# DRIVERS.net
KiCad netlist of a schematic drawn in Altium Designer
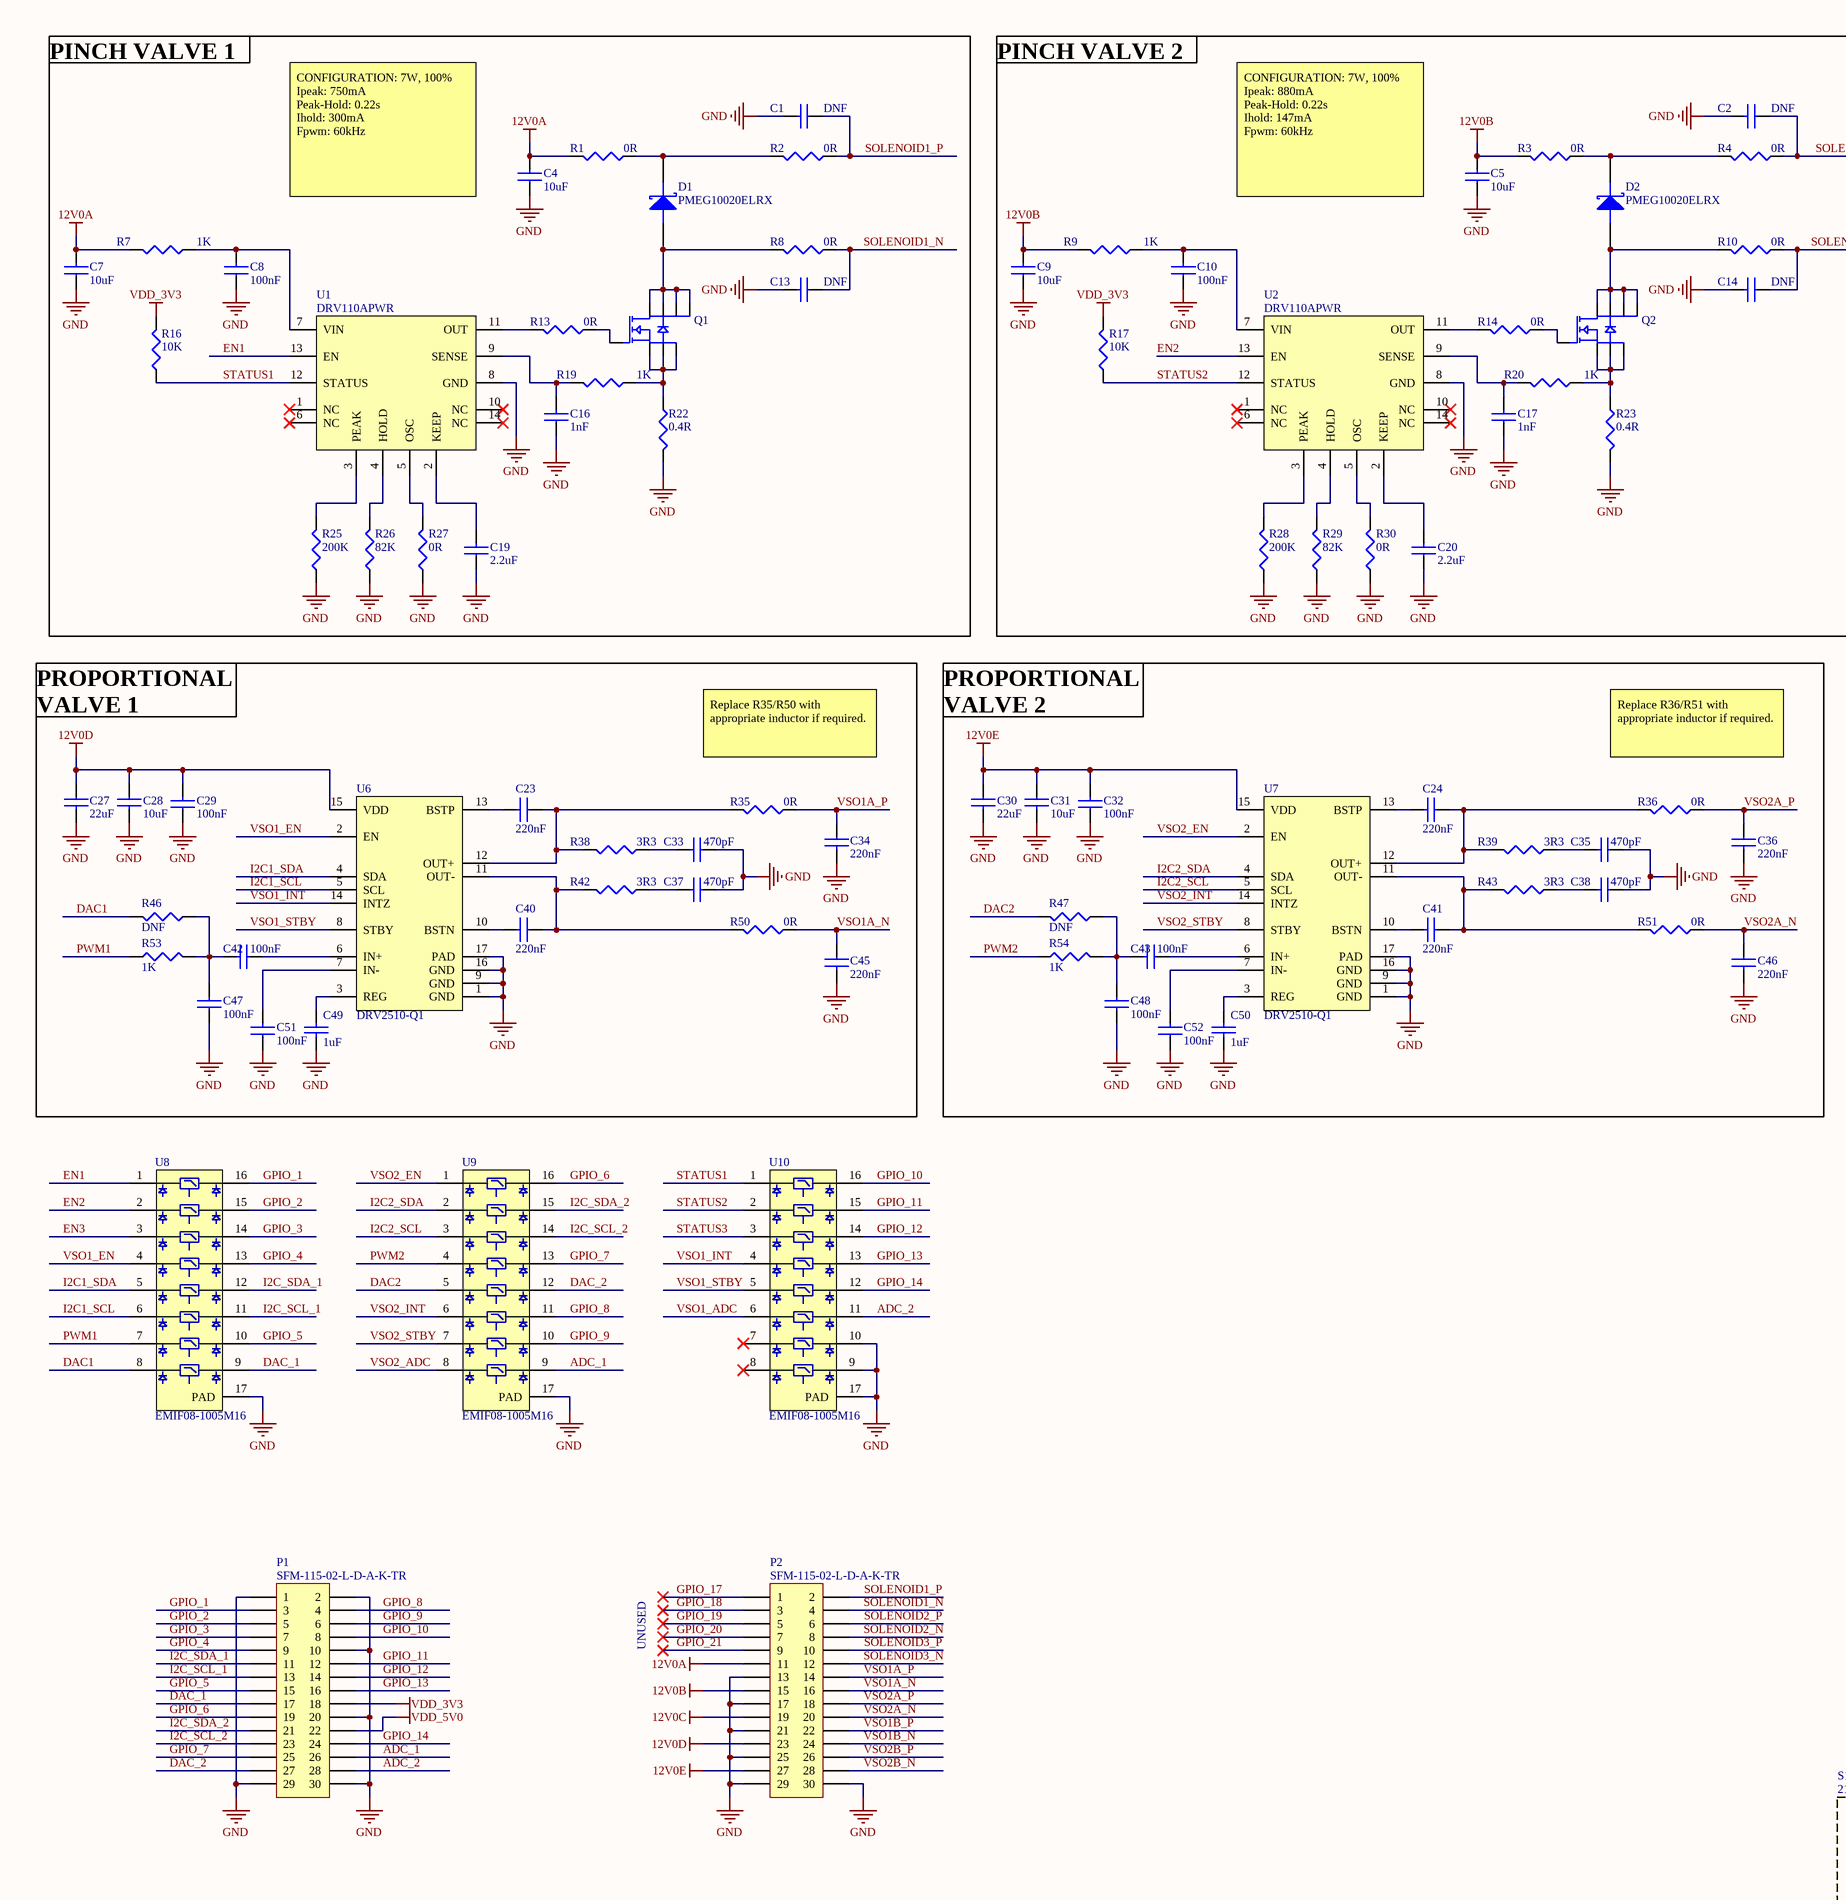
[diagram p0: DRIVERS.SchDoc, left]
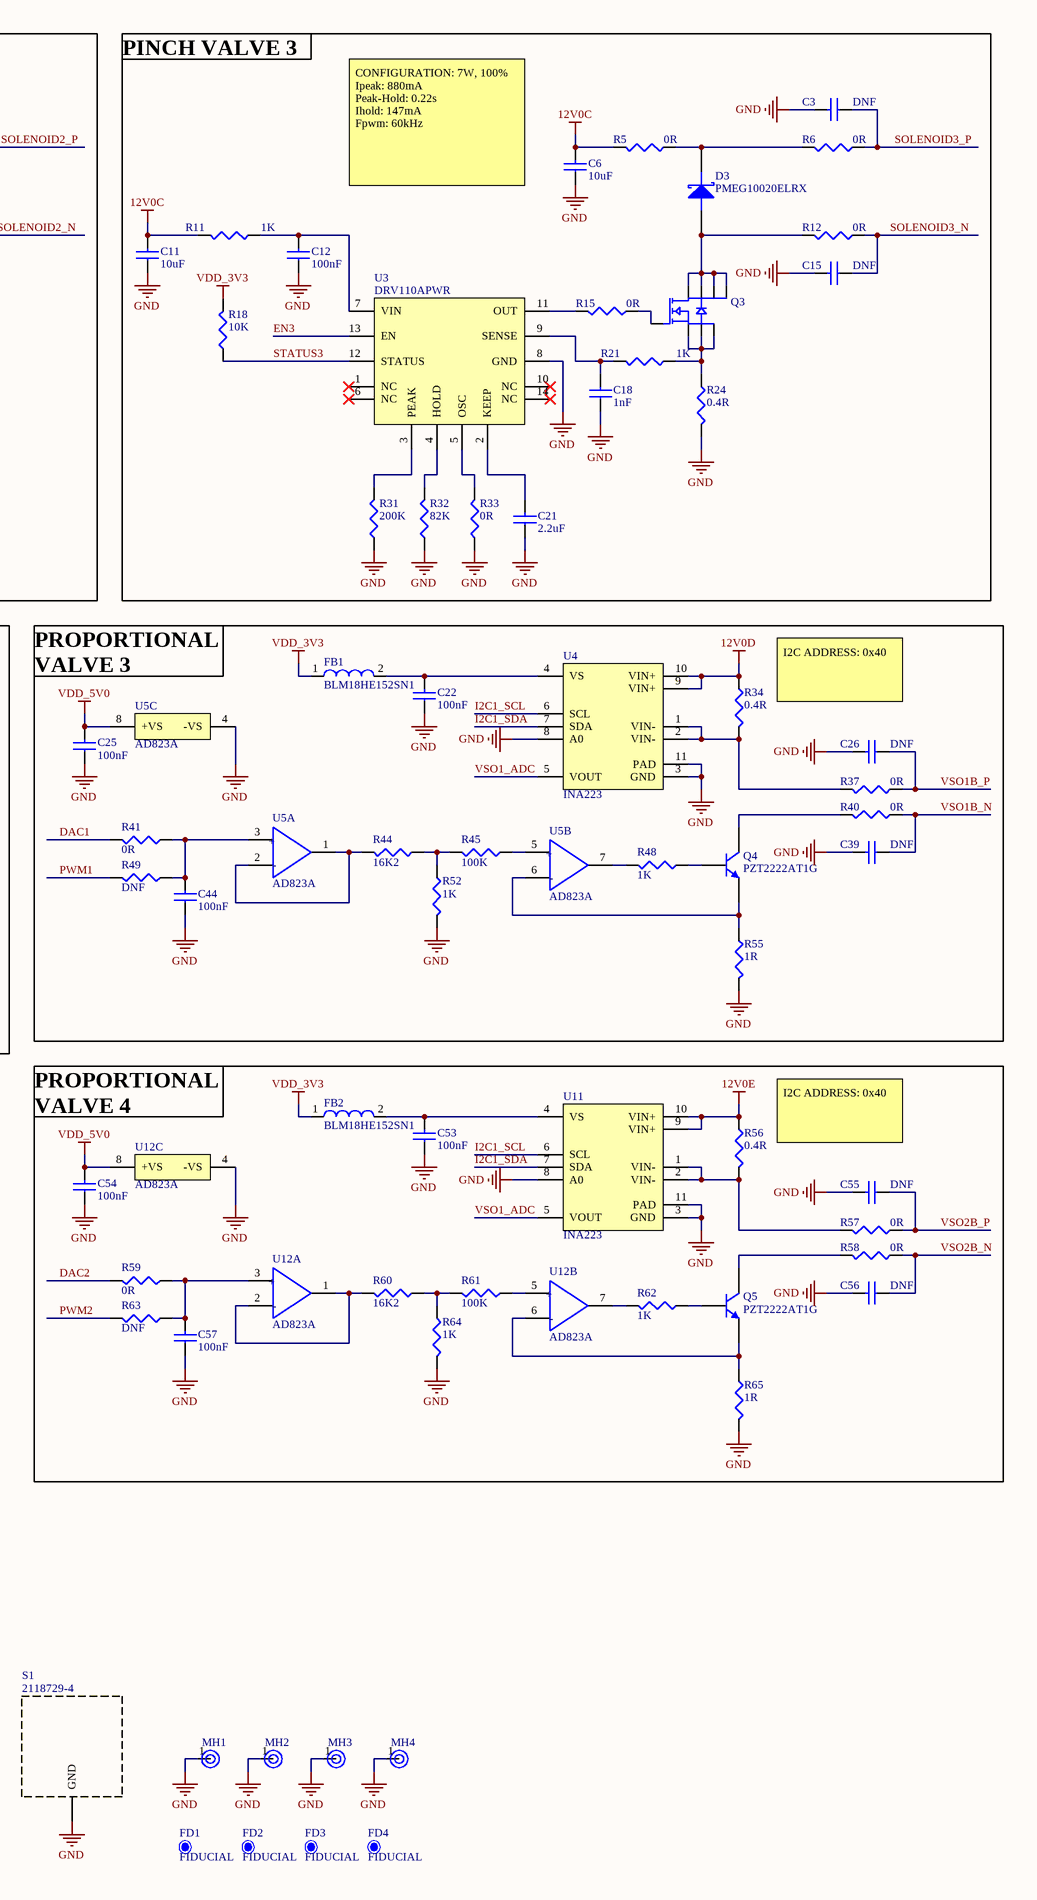
[diagram p1: DRIVERS.SchDoc, right]

(export (version "E")
  (design (tool "Eeschema 10.0.6"))
  (components
    (comp (ref "C1")
      (value "DNF")
      (footprint "CC0402")
      (description "CAP CER 0.001UF 50V 10% X7R 0402")
      (fields (field (name "MANUFACTURER") "Murata") (field (name "PARTNUMBER") "GCM155R71H102KA37D"))
      (libsource (lib "ERD TiAm") (part "CAP CER 0.1UF 10V 10% X5R 0402"))
    )
    (comp (ref "C2")
      (value "DNF")
      (footprint "CC0402")
      (description "CAP CER 0.001UF 50V 10% X7R 0402")
      (fields (field (name "MANUFACTURER") "Murata") (field (name "PARTNUMBER") "GCM155R71H102KA37D"))
      (libsource (lib "ERD TiAm") (part "CAP CER 0.1UF 10V 10% X5R 0402"))
    )
    (comp (ref "C3")
      (value "DNF")
      (footprint "CC0402")
      (description "CAP CER 0.001UF 50V 10% X7R 0402")
      (fields (field (name "MANUFACTURER") "Murata") (field (name "PARTNUMBER") "GCM155R71H102KA37D"))
      (libsource (lib "ERD TiAm") (part "CAP CER 0.1UF 10V 10% X5R 0402"))
    )
    (comp (ref "C4")
      (value "10uF")
      (footprint "CC0603")
      (description "CAP CER 10UF 25V 20% X5R 0603")
      (fields (field (name "MANUFACTURER") "Murata") (field (name "PARTNUMBER") "GRM188R61E106MA73D"))
      (libsource (lib "ERD TiAm") (part "CAP CER 0.1UF 10V 10% X5R 0402"))
    )
    (comp (ref "C5")
      (value "10uF")
      (footprint "CC0603")
      (description "CAP CER 10UF 25V 20% X5R 0603")
      (fields (field (name "MANUFACTURER") "Murata") (field (name "PARTNUMBER") "GRM188R61E106MA73D"))
      (libsource (lib "ERD TiAm") (part "CAP CER 0.1UF 10V 10% X5R 0402"))
    )
    (comp (ref "C6")
      (value "10uF")
      (footprint "CC0603")
      (description "CAP CER 10UF 25V 20% X5R 0603")
      (fields (field (name "MANUFACTURER") "Murata") (field (name "PARTNUMBER") "GRM188R61E106MA73D"))
      (libsource (lib "ERD TiAm") (part "CAP CER 0.1UF 10V 10% X5R 0402"))
    )
    (comp (ref "C7")
      (value "10uF")
      (footprint "CC0603")
      (description "CAP CER 10UF 25V 20% X5R 0603")
      (fields (field (name "MANUFACTURER") "Murata") (field (name "PARTNUMBER") "GRM188R61E106MA73D"))
      (libsource (lib "ERD TiAm") (part "CAP CER 0.1UF 10V 10% X5R 0402"))
    )
    (comp (ref "C8")
      (value "100nF")
      (footprint "CC0402")
      (description "CAP CER 0.1UF 50V 10% X7R 0402")
      (fields (field (name "MANUFACTURER") "Murata") (field (name "PARTNUMBER") "GCM155R71H104KE02D"))
      (libsource (lib "ERD TiAm") (part "CAP CER 0.1UF 10V 10% X5R 0402"))
    )
    (comp (ref "C9")
      (value "10uF")
      (footprint "CC0603")
      (description "CAP CER 10UF 25V 20% X5R 0603")
      (fields (field (name "MANUFACTURER") "Murata") (field (name "PARTNUMBER") "GRM188R61E106MA73D"))
      (libsource (lib "ERD TiAm") (part "CAP CER 0.1UF 10V 10% X5R 0402"))
    )
    (comp (ref "C10")
      (value "100nF")
      (footprint "CC0402")
      (description "CAP CER 0.1UF 50V 10% X7R 0402")
      (fields (field (name "MANUFACTURER") "Murata") (field (name "PARTNUMBER") "GCM155R71H104KE02D"))
      (libsource (lib "ERD TiAm") (part "CAP CER 0.1UF 10V 10% X5R 0402"))
    )
    (comp (ref "C11")
      (value "10uF")
      (footprint "CC0603")
      (description "CAP CER 10UF 25V 20% X5R 0603")
      (fields (field (name "MANUFACTURER") "Murata") (field (name "PARTNUMBER") "GRM188R61E106MA73D"))
      (libsource (lib "ERD TiAm") (part "CAP CER 0.1UF 10V 10% X5R 0402"))
    )
    (comp (ref "C12")
      (value "100nF")
      (footprint "CC0402")
      (description "CAP CER 0.1UF 50V 10% X7R 0402")
      (fields (field (name "MANUFACTURER") "Murata") (field (name "PARTNUMBER") "GCM155R71H104KE02D"))
      (libsource (lib "ERD TiAm") (part "CAP CER 0.1UF 10V 10% X5R 0402"))
    )
    (comp (ref "C13")
      (value "DNF")
      (footprint "CC0402")
      (description "CAP CER 0.001UF 50V 10% X7R 0402")
      (fields (field (name "MANUFACTURER") "Murata") (field (name "PARTNUMBER") "GCM155R71H102KA37D"))
      (libsource (lib "ERD TiAm") (part "CAP CER 0.1UF 10V 10% X5R 0402"))
    )
    (comp (ref "C14")
      (value "DNF")
      (footprint "CC0402")
      (description "CAP CER 0.001UF 50V 10% X7R 0402")
      (fields (field (name "MANUFACTURER") "Murata") (field (name "PARTNUMBER") "GCM155R71H102KA37D"))
      (libsource (lib "ERD TiAm") (part "CAP CER 0.1UF 10V 10% X5R 0402"))
    )
    (comp (ref "C15")
      (value "DNF")
      (footprint "CC0402")
      (description "CAP CER 0.001UF 50V 10% X7R 0402")
      (fields (field (name "MANUFACTURER") "Murata") (field (name "PARTNUMBER") "GCM155R71H102KA37D"))
      (libsource (lib "ERD TiAm") (part "CAP CER 0.1UF 10V 10% X5R 0402"))
    )
    (comp (ref "C16")
      (value "1nF")
      (footprint "CC0402")
      (description "CAP CER 0.001UF 50V 10% X7R 0402")
      (fields (field (name "MANUFACTURER") "Murata") (field (name "PARTNUMBER") "GCM155R71H102KA37D"))
      (libsource (lib "ERD TiAm") (part "CAP CER 0.1UF 10V 10% X5R 0402"))
    )
    (comp (ref "C17")
      (value "1nF")
      (footprint "CC0402")
      (description "CAP CER 0.001UF 50V 10% X7R 0402")
      (fields (field (name "MANUFACTURER") "Murata") (field (name "PARTNUMBER") "GCM155R71H102KA37D"))
      (libsource (lib "ERD TiAm") (part "CAP CER 0.1UF 10V 10% X5R 0402"))
    )
    (comp (ref "C18")
      (value "1nF")
      (footprint "CC0402")
      (description "CAP CER 0.001UF 50V 10% X7R 0402")
      (fields (field (name "MANUFACTURER") "Murata") (field (name "PARTNUMBER") "GCM155R71H102KA37D"))
      (libsource (lib "ERD TiAm") (part "CAP CER 0.1UF 10V 10% X5R 0402"))
    )
    (comp (ref "C19")
      (value "2.2uF")
      (footprint "CC0603")
      (description "CAP CER 2.2UF 25V 10% X5R 0603")
      (fields (field (name "MANUFACTURER") "Murata") (field (name "PARTNUMBER") "GRM188R61E225KA12D"))
      (libsource (lib "ERD TiAm") (part "CAP CER 0.1UF 10V 10% X5R 0402"))
    )
    (comp (ref "C20")
      (value "2.2uF")
      (footprint "CC0603")
      (description "CAP CER 2.2UF 25V 10% X5R 0603")
      (fields (field (name "MANUFACTURER") "Murata") (field (name "PARTNUMBER") "GRM188R61E225KA12D"))
      (libsource (lib "ERD TiAm") (part "CAP CER 0.1UF 10V 10% X5R 0402"))
    )
    (comp (ref "C21")
      (value "2.2uF")
      (footprint "CC0603")
      (description "CAP CER 2.2UF 25V 10% X5R 0603")
      (fields (field (name "MANUFACTURER") "Murata") (field (name "PARTNUMBER") "GRM188R61E225KA12D"))
      (libsource (lib "ERD TiAm") (part "CAP CER 0.1UF 10V 10% X5R 0402"))
    )
    (comp (ref "C22")
      (value "100nF")
      (footprint "CC0402")
      (description "CAP CER 0.1UF 50V 10% X7R 0402")
      (fields (field (name "MANUFACTURER") "Murata") (field (name "PARTNUMBER") "GCM155R71H104KE02D"))
      (libsource (lib "ERD TiAm") (part "CAP CER 0.1UF 10V 10% X5R 0402"))
    )
    (comp (ref "C23")
      (value "220nF")
      (footprint "CC0603")
      (description "CAP CER 0.22UF 25V 10% X7R 0603")
      (fields (field (name "MANUFACTURER") "Murata") (field (name "PARTNUMBER") "GRM188R71E224KA88D"))
      (libsource (lib "ERD TiAm") (part "CAP CER 0.1UF 10V 10% X5R 0402"))
    )
    (comp (ref "C24")
      (value "220nF")
      (footprint "CC0603")
      (description "CAP CER 0.22UF 25V 10% X7R 0603")
      (fields (field (name "MANUFACTURER") "Murata") (field (name "PARTNUMBER") "GRM188R71E224KA88D"))
      (libsource (lib "ERD TiAm") (part "CAP CER 0.1UF 10V 10% X5R 0402"))
    )
    (comp (ref "C25")
      (value "100nF")
      (footprint "CC0402")
      (description "CAP CER 0.1UF 50V 10% X7R 0402")
      (fields (field (name "MANUFACTURER") "Murata") (field (name "PARTNUMBER") "GCM155R71H104KE02D"))
      (libsource (lib "ERD TiAm") (part "CAP CER 0.1UF 10V 10% X5R 0402"))
    )
    (comp (ref "C26")
      (value "DNF")
      (footprint "CC0402")
      (description "CAP CER 0.001UF 50V 10% X7R 0402")
      (fields (field (name "MANUFACTURER") "Murata") (field (name "PARTNUMBER") "GCM155R71H102KA37D"))
      (libsource (lib "ERD TiAm") (part "CAP CER 0.1UF 10V 10% X5R 0402"))
    )
    (comp (ref "C27")
      (value "22uF")
      (footprint "CC0805")
      (description "CAP CER 22UF 25V 20% X5R 0805")
      (fields (field (name "MANUFACTURER") "Murata") (field (name "PARTNUMBER") "GRM21BR61E226ME44K"))
      (libsource (lib "ERD TiAm") (part "CAP CER 0.1UF 10V 10% X5R 0402"))
    )
    (comp (ref "C28")
      (value "10uF")
      (footprint "CC0603")
      (description "CAP CER 10UF 25V 20% X5R 0603")
      (fields (field (name "MANUFACTURER") "Murata") (field (name "PARTNUMBER") "GRM188R61E106MA73D"))
      (libsource (lib "ERD TiAm") (part "CAP CER 0.1UF 10V 10% X5R 0402"))
    )
    (comp (ref "C29")
      (value "100nF")
      (footprint "CC0402")
      (description "CAP CER 0.1UF 50V 10% X7R 0402")
      (fields (field (name "MANUFACTURER") "Murata") (field (name "PARTNUMBER") "GCM155R71H104KE02D"))
      (libsource (lib "ERD TiAm") (part "CAP CER 0.1UF 10V 10% X5R 0402"))
    )
    (comp (ref "C30")
      (value "22uF")
      (footprint "CC0805")
      (description "CAP CER 22UF 25V 20% X5R 0805")
      (fields (field (name "MANUFACTURER") "Murata") (field (name "PARTNUMBER") "GRM21BR61E226ME44K"))
      (libsource (lib "ERD TiAm") (part "CAP CER 0.1UF 10V 10% X5R 0402"))
    )
    (comp (ref "C31")
      (value "10uF")
      (footprint "CC0603")
      (description "CAP CER 10UF 25V 20% X5R 0603")
      (fields (field (name "MANUFACTURER") "Murata") (field (name "PARTNUMBER") "GRM188R61E106MA73D"))
      (libsource (lib "ERD TiAm") (part "CAP CER 0.1UF 10V 10% X5R 0402"))
    )
    (comp (ref "C32")
      (value "100nF")
      (footprint "CC0402")
      (description "CAP CER 0.1UF 50V 10% X7R 0402")
      (fields (field (name "MANUFACTURER") "Murata") (field (name "PARTNUMBER") "GCM155R71H104KE02D"))
      (libsource (lib "ERD TiAm") (part "CAP CER 0.1UF 10V 10% X5R 0402"))
    )
    (comp (ref "C33")
      (value "470pF")
      (footprint "CC0603")
      (description "CAP CER 470PF 50V 5% C0G/NP0 0402")
      (fields (field (name "MANUFACTURER") "Murata") (field (name "PARTNUMBER") "GRM1555C1H471JA01D"))
      (libsource (lib "ERD TiAm") (part "CAP CER 0.1UF 10V 10% X5R 0402"))
    )
    (comp (ref "C34")
      (value "220nF")
      (footprint "CC0603")
      (description "CAP CER 0.22UF 25V 10% X7R 0603")
      (fields (field (name "MANUFACTURER") "Murata") (field (name "PARTNUMBER") "GRM188R71E224KA88D"))
      (libsource (lib "ERD TiAm") (part "CAP CER 0.1UF 10V 10% X5R 0402"))
    )
    (comp (ref "C35")
      (value "470pF")
      (footprint "CC0603")
      (description "CAP CER 470PF 50V 5% C0G/NP0 0402")
      (fields (field (name "MANUFACTURER") "Murata") (field (name "PARTNUMBER") "GRM1555C1H471JA01D"))
      (libsource (lib "ERD TiAm") (part "CAP CER 0.1UF 10V 10% X5R 0402"))
    )
    (comp (ref "C36")
      (value "220nF")
      (footprint "CC0603")
      (description "CAP CER 0.22UF 25V 10% X7R 0603")
      (fields (field (name "MANUFACTURER") "Murata") (field (name "PARTNUMBER") "GRM188R71E224KA88D"))
      (libsource (lib "ERD TiAm") (part "CAP CER 0.1UF 10V 10% X5R 0402"))
    )
    (comp (ref "C37")
      (value "470pF")
      (footprint "CC0603")
      (description "CAP CER 470PF 50V 5% C0G/NP0 0402")
      (fields (field (name "MANUFACTURER") "Murata") (field (name "PARTNUMBER") "GRM1555C1H471JA01D"))
      (libsource (lib "ERD TiAm") (part "CAP CER 0.1UF 10V 10% X5R 0402"))
    )
    (comp (ref "C38")
      (value "470pF")
      (footprint "CC0603")
      (description "CAP CER 470PF 50V 5% C0G/NP0 0402")
      (fields (field (name "MANUFACTURER") "Murata") (field (name "PARTNUMBER") "GRM1555C1H471JA01D"))
      (libsource (lib "ERD TiAm") (part "CAP CER 0.1UF 10V 10% X5R 0402"))
    )
    (comp (ref "C39")
      (value "DNF")
      (footprint "CC0402")
      (description "CAP CER 0.001UF 50V 10% X7R 0402")
      (fields (field (name "MANUFACTURER") "Murata") (field (name "PARTNUMBER") "GCM155R71H102KA37D"))
      (libsource (lib "ERD TiAm") (part "CAP CER 0.1UF 10V 10% X5R 0402"))
    )
    (comp (ref "C40")
      (value "220nF")
      (footprint "CC0603")
      (description "CAP CER 0.22UF 25V 10% X7R 0603")
      (fields (field (name "MANUFACTURER") "Murata") (field (name "PARTNUMBER") "GRM188R71E224KA88D"))
      (libsource (lib "ERD TiAm") (part "CAP CER 0.1UF 10V 10% X5R 0402"))
    )
    (comp (ref "C41")
      (value "220nF")
      (footprint "CC0603")
      (description "CAP CER 0.22UF 25V 10% X7R 0603")
      (fields (field (name "MANUFACTURER") "Murata") (field (name "PARTNUMBER") "GRM188R71E224KA88D"))
      (libsource (lib "ERD TiAm") (part "CAP CER 0.1UF 10V 10% X5R 0402"))
    )
    (comp (ref "C42")
      (value "100nF")
      (footprint "CC0402")
      (description "CAP CER 0.1UF 50V 10% X7R 0402")
      (fields (field (name "MANUFACTURER") "Murata") (field (name "PARTNUMBER") "GCM155R71H104KE02D"))
      (libsource (lib "ERD TiAm") (part "CAP CER 0.1UF 10V 10% X5R 0402"))
    )
    (comp (ref "C43")
      (value "100nF")
      (footprint "CC0402")
      (description "CAP CER 0.1UF 50V 10% X7R 0402")
      (fields (field (name "MANUFACTURER") "Murata") (field (name "PARTNUMBER") "GCM155R71H104KE02D"))
      (libsource (lib "ERD TiAm") (part "CAP CER 0.1UF 10V 10% X5R 0402"))
    )
    (comp (ref "C44")
      (value "100nF")
      (footprint "CC0402")
      (description "CAP CER 0.1UF 50V 10% X7R 0402")
      (fields (field (name "MANUFACTURER") "Murata") (field (name "PARTNUMBER") "GCM155R71H104KE02D"))
      (libsource (lib "ERD TiAm") (part "CAP CER 0.1UF 10V 10% X5R 0402"))
    )
    (comp (ref "C45")
      (value "220nF")
      (footprint "CC0603")
      (description "CAP CER 0.22UF 25V 10% X7R 0603")
      (fields (field (name "MANUFACTURER") "Murata") (field (name "PARTNUMBER") "GRM188R71E224KA88D"))
      (libsource (lib "ERD TiAm") (part "CAP CER 0.1UF 10V 10% X5R 0402"))
    )
    (comp (ref "C46")
      (value "220nF")
      (footprint "CC0603")
      (description "CAP CER 0.22UF 25V 10% X7R 0603")
      (fields (field (name "MANUFACTURER") "Murata") (field (name "PARTNUMBER") "GRM188R71E224KA88D"))
      (libsource (lib "ERD TiAm") (part "CAP CER 0.1UF 10V 10% X5R 0402"))
    )
    (comp (ref "C47")
      (value "100nF")
      (footprint "CC0402")
      (description "CAP CER 0.1UF 50V 10% X7R 0402")
      (fields (field (name "MANUFACTURER") "Murata") (field (name "PARTNUMBER") "GCM155R71H104KE02D"))
      (libsource (lib "ERD TiAm") (part "CAP CER 0.1UF 10V 10% X5R 0402"))
    )
    (comp (ref "C48")
      (value "100nF")
      (footprint "CC0402")
      (description "CAP CER 0.1UF 50V 10% X7R 0402")
      (fields (field (name "MANUFACTURER") "Murata") (field (name "PARTNUMBER") "GCM155R71H104KE02D"))
      (libsource (lib "ERD TiAm") (part "CAP CER 0.1UF 10V 10% X5R 0402"))
    )
    (comp (ref "C49")
      (value "1uF")
      (footprint "CC0402")
      (description "CAP CER 1.0UF 10V 10% X5R 0402")
      (fields (field (name "PARTNUMBER") "GRM153R61A105ME95D"))
      (libsource (lib "*") (part "CAPCERAMIC"))
    )
    (comp (ref "C50")
      (value "1uF")
      (footprint "CC0402")
      (description "CAP CER 1.0UF 10V 10% X5R 0402")
      (fields (field (name "PARTNUMBER") "GRM153R61A105ME95D"))
      (libsource (lib "*") (part "CAPCERAMIC"))
    )
    (comp (ref "C51")
      (value "100nF")
      (footprint "CC0402")
      (description "CAP CER 0.1UF 50V 10% X7R 0402")
      (fields (field (name "MANUFACTURER") "Murata") (field (name "PARTNUMBER") "GCM155R71H104KE02D"))
      (libsource (lib "ERD TiAm") (part "CAP CER 0.1UF 10V 10% X5R 0402"))
    )
    (comp (ref "C52")
      (value "100nF")
      (footprint "CC0402")
      (description "CAP CER 0.1UF 50V 10% X7R 0402")
      (fields (field (name "MANUFACTURER") "Murata") (field (name "PARTNUMBER") "GCM155R71H104KE02D"))
      (libsource (lib "ERD TiAm") (part "CAP CER 0.1UF 10V 10% X5R 0402"))
    )
    (comp (ref "C53")
      (value "100nF")
      (footprint "CC0402")
      (description "CAP CER 0.1UF 50V 10% X7R 0402")
      (fields (field (name "MANUFACTURER") "Murata") (field (name "PARTNUMBER") "GCM155R71H104KE02D"))
      (libsource (lib "ERD TiAm") (part "CAP CER 0.1UF 10V 10% X5R 0402"))
    )
    (comp (ref "C54")
      (value "100nF")
      (footprint "CC0402")
      (description "CAP CER 0.1UF 50V 10% X7R 0402")
      (fields (field (name "MANUFACTURER") "Murata") (field (name "PARTNUMBER") "GCM155R71H104KE02D"))
      (libsource (lib "ERD TiAm") (part "CAP CER 0.1UF 10V 10% X5R 0402"))
    )
    (comp (ref "C55")
      (value "DNF")
      (footprint "CC0402")
      (description "CAP CER 0.001UF 50V 10% X7R 0402")
      (fields (field (name "MANUFACTURER") "Murata") (field (name "PARTNUMBER") "GCM155R71H102KA37D"))
      (libsource (lib "ERD TiAm") (part "CAP CER 0.1UF 10V 10% X5R 0402"))
    )
    (comp (ref "C56")
      (value "DNF")
      (footprint "CC0402")
      (description "CAP CER 0.001UF 50V 10% X7R 0402")
      (fields (field (name "MANUFACTURER") "Murata") (field (name "PARTNUMBER") "GCM155R71H102KA37D"))
      (libsource (lib "ERD TiAm") (part "CAP CER 0.1UF 10V 10% X5R 0402"))
    )
    (comp (ref "C57")
      (value "100nF")
      (footprint "CC0402")
      (description "CAP CER 0.1UF 50V 10% X7R 0402")
      (fields (field (name "MANUFACTURER") "Murata") (field (name "PARTNUMBER") "GCM155R71H104KE02D"))
      (libsource (lib "ERD TiAm") (part "CAP CER 0.1UF 10V 10% X5R 0402"))
    )
    (comp (ref "D1")
      (value "PMEG10020ELRX")
      (footprint "SOD123W")
      (description "DIODE, SCHOTTKY, 100V, 2A, 3.7ns, SOD123W")
      (libsource (lib "GadgetJD") (part "DIODE SCHOTTKY"))
    )
    (comp (ref "D2")
      (value "PMEG10020ELRX")
      (footprint "SOD123W")
      (description "DIODE, SCHOTTKY, 100V, 2A, 3.7ns, SOD123W")
      (libsource (lib "GadgetJD") (part "DIODE SCHOTTKY"))
    )
    (comp (ref "D3")
      (value "PMEG10020ELRX")
      (footprint "SOD123W")
      (description "DIODE, SCHOTTKY, 100V, 2A, 3.7ns, SOD123W")
      (libsource (lib "GadgetJD") (part "DIODE SCHOTTKY"))
    )
    (comp (ref "FB1")
      (value "BLM18HE152SN1")
      (footprint "LC0603")
      (description "FERRITE, 500mA, 500mOHM, 0603")
      (libsource (lib "BEAGLEBONEBLACK_REV A5B") (part "FER_180_200_0"))
    )
    (comp (ref "FB2")
      (value "BLM18HE152SN1")
      (footprint "LC0603")
      (description "FERRITE, 500mA, 500mOHM, 0603")
      (libsource (lib "BEAGLEBONEBLACK_REV A5B") (part "FER_180_200_0"))
    )
    (comp (ref "FD1")
      (value "FIDUCIAL")
      (footprint "FIDUCIAL")
      (description "Fiducial 2mm")
      (fields (field (name "PARTNUMBER") "NA"))
      (libsource (lib "*") (part "FIDUCIAL"))
    )
    (comp (ref "FD2")
      (value "FIDUCIAL")
      (footprint "FIDUCIAL")
      (description "Fiducial 2mm")
      (fields (field (name "PARTNUMBER") "NA"))
      (libsource (lib "*") (part "FIDUCIAL"))
    )
    (comp (ref "FD3")
      (value "FIDUCIAL")
      (footprint "FIDUCIAL")
      (description "Fiducial 2mm")
      (fields (field (name "PARTNUMBER") "NA"))
      (libsource (lib "*") (part "FIDUCIAL"))
    )
    (comp (ref "FD4")
      (value "FIDUCIAL")
      (footprint "FIDUCIAL")
      (description "Fiducial 2mm")
      (fields (field (name "PARTNUMBER") "NA"))
      (libsource (lib "*") (part "FIDUCIAL"))
    )
    (comp (ref "MH1")
      (value "MH")
      (footprint "MH - M3")
      (description "Mounting Hole")
      (fields (field (name "PARTNUMBER") "NA"))
      (libsource (lib "BCI_rev_0") (part "MountingHole"))
    )
    (comp (ref "MH2")
      (value "MH")
      (footprint "MH - M3")
      (description "Mounting Hole")
      (fields (field (name "PARTNUMBER") "NA"))
      (libsource (lib "BCI_rev_0") (part "MountingHole"))
    )
    (comp (ref "MH3")
      (value "MH")
      (footprint "MH - M3")
      (description "Mounting Hole")
      (fields (field (name "PARTNUMBER") "NA"))
      (libsource (lib "BCI_rev_0") (part "MountingHole"))
    )
    (comp (ref "MH4")
      (value "MH")
      (footprint "MH - M3")
      (description "Mounting Hole")
      (fields (field (name "PARTNUMBER") "NA"))
      (libsource (lib "BCI_rev_0") (part "MountingHole"))
    )
    (comp (ref "P1")
      (value "SFM-115-02-L-D-A-K-TR")
      (footprint "ERD TiAm:SFM-115-02-L-D-A-K-TR")
      (description "Receptacle, 30 POS, 1.27mm PITCH, SMD")
      (libsource (lib "Miscellaneous Connectors") (part "Header 15X2"))
    )
    (comp (ref "P2")
      (value "SFM-115-02-L-D-A-K-TR")
      (footprint "ERD TiAm:SFM-115-02-L-D-A-K-TR")
      (description "Receptacle, 30 POS, 1.27mm PITCH, SMD")
      (libsource (lib "Miscellaneous Connectors") (part "Header 15X2"))
    )
    (comp (ref "Q1")
      (value "BSC054N04NSGATMA1")
      (footprint "PG-TDSON-8 - alternate")
      (description "N-channel FET, 40V, 17A, 5.4mOhm, TDSON-8")
      (libsource (lib "SCH") (part "BSC190N15NS3"))
    )
    (comp (ref "Q2")
      (value "BSC054N04NSGATMA1")
      (footprint "PG-TDSON-8 - alternate")
      (description "N-channel FET, 40V, 17A, 5.4mOhm, TDSON-8")
      (libsource (lib "SCH") (part "BSC190N15NS3"))
    )
    (comp (ref "Q3")
      (value "BSC054N04NSGATMA1")
      (footprint "PG-TDSON-8 - alternate")
      (description "N-channel FET, 40V, 17A, 5.4mOhm, TDSON-8")
      (libsource (lib "SCH") (part "BSC190N15NS3"))
    )
    (comp (ref "Q4")
      (value "PZT2222AT1G")
      (footprint "ERD TiAm:SOT223")
      (description "NPN BJT, 600 mA, 40V, SOT223")
      (fields (field (name "MANUFACTURER") "ON Semiconductor"))
      (libsource (lib "Miscellaneous Devices") (part "NPN"))
    )
    (comp (ref "Q5")
      (value "PZT2222AT1G")
      (footprint "ERD TiAm:SOT223")
      (description "NPN BJT, 600 mA, 40V, SOT223")
      (fields (field (name "MANUFACTURER") "ON Semiconductor"))
      (libsource (lib "Miscellaneous Devices") (part "NPN"))
    )
    (comp (ref "R1")
      (value "0R")
      (footprint "RC0603")
      (description "RES, 0 OHM, 1/10W, 50mOhm (5%), 0603")
      (fields (field (name "MANUFACTURER") "Yageo") (field (name "PARTNUMBER") "RC0603JR-070RP"))
      (libsource (lib "ERD TiAm") (part "RES_10K_1/16W_1%_0402"))
    )
    (comp (ref "R2")
      (value "0R")
      (footprint "RC0603")
      (description "RES, 0 OHM, 1/10W, 50mOhm (5%), 0603")
      (fields (field (name "MANUFACTURER") "Yageo") (field (name "PARTNUMBER") "RC0603JR-070RP"))
      (libsource (lib "ERD TiAm") (part "RES_10K_1/16W_1%_0402"))
    )
    (comp (ref "R3")
      (value "0R")
      (footprint "RC0603")
      (description "RES, 0 OHM, 1/10W, 50mOhm (5%), 0603")
      (fields (field (name "MANUFACTURER") "Yageo") (field (name "PARTNUMBER") "RC0603JR-070RP"))
      (libsource (lib "ERD TiAm") (part "RES_10K_1/16W_1%_0402"))
    )
    (comp (ref "R4")
      (value "0R")
      (footprint "RC0603")
      (description "RES, 0 OHM, 1/10W, 50mOhm (5%), 0603")
      (fields (field (name "MANUFACTURER") "Yageo") (field (name "PARTNUMBER") "RC0603JR-070RP"))
      (libsource (lib "ERD TiAm") (part "RES_10K_1/16W_1%_0402"))
    )
    (comp (ref "R5")
      (value "0R")
      (footprint "RC0603")
      (description "RES, 0 OHM, 1/10W, 50mOhm (5%), 0603")
      (fields (field (name "MANUFACTURER") "Yageo") (field (name "PARTNUMBER") "RC0603JR-070RP"))
      (libsource (lib "ERD TiAm") (part "RES_10K_1/16W_1%_0402"))
    )
    (comp (ref "R6")
      (value "0R")
      (footprint "RC0603")
      (description "RES, 0 OHM, 1/10W, 50mOhm (5%), 0603")
      (fields (field (name "MANUFACTURER") "Yageo") (field (name "PARTNUMBER") "RC0603JR-070RP"))
      (libsource (lib "ERD TiAm") (part "RES_10K_1/16W_1%_0402"))
    )
    (comp (ref "R7")
      (value "1K")
      (footprint "RC0402")
      (description "RES, 1K OHM, 1/16W, 1%, 0402")
      (fields (field (name "MANUFACTURER") "Yageo") (field (name "PARTNUMBER") "RC0402FR-071KL"))
      (libsource (lib "ERD TiAm") (part "RES_10K_1/16W_1%_0402"))
    )
    (comp (ref "R8")
      (value "0R")
      (footprint "RC0603")
      (description "RES, 0 OHM, 1/10W, 50mOhm (5%), 0603")
      (fields (field (name "MANUFACTURER") "Yageo") (field (name "PARTNUMBER") "RC0603JR-070RP"))
      (libsource (lib "ERD TiAm") (part "RES_10K_1/16W_1%_0402"))
    )
    (comp (ref "R9")
      (value "1K")
      (footprint "RC0402")
      (description "RES, 1K OHM, 1/16W, 1%, 0402")
      (fields (field (name "MANUFACTURER") "Yageo") (field (name "PARTNUMBER") "RC0402FR-071KL"))
      (libsource (lib "ERD TiAm") (part "RES_10K_1/16W_1%_0402"))
    )
    (comp (ref "R10")
      (value "0R")
      (footprint "RC0603")
      (description "RES, 0 OHM, 1/10W, 50mOhm (5%), 0603")
      (fields (field (name "MANUFACTURER") "Yageo") (field (name "PARTNUMBER") "RC0603JR-070RP"))
      (libsource (lib "ERD TiAm") (part "RES_10K_1/16W_1%_0402"))
    )
    (comp (ref "R11")
      (value "1K")
      (footprint "RC0402")
      (description "RES, 1K OHM, 1/16W, 1%, 0402")
      (fields (field (name "MANUFACTURER") "Yageo") (field (name "PARTNUMBER") "RC0402FR-071KL"))
      (libsource (lib "ERD TiAm") (part "RES_10K_1/16W_1%_0402"))
    )
    (comp (ref "R12")
      (value "0R")
      (footprint "RC0603")
      (description "RES, 0 OHM, 1/10W, 50mOhm (5%), 0603")
      (fields (field (name "MANUFACTURER") "Yageo") (field (name "PARTNUMBER") "RC0603JR-070RP"))
      (libsource (lib "ERD TiAm") (part "RES_10K_1/16W_1%_0402"))
    )
    (comp (ref "R13")
      (value "0R")
      (footprint "RC0402")
      (description "RES, 0 OHM, 1/16W, 1%, 0402")
      (fields (field (name "MANUFACTURER") "Yageo") (field (name "PARTNUMBER") "RC0402FR-070RL"))
      (libsource (lib "ERD TiAm") (part "RES_10K_1/16W_1%_0402"))
    )
    (comp (ref "R14")
      (value "0R")
      (footprint "RC0402")
      (description "RES, 0 OHM, 1/16W, 1%, 0402")
      (fields (field (name "MANUFACTURER") "Yageo") (field (name "PARTNUMBER") "RC0402FR-070RL"))
      (libsource (lib "ERD TiAm") (part "RES_10K_1/16W_1%_0402"))
    )
    (comp (ref "R15")
      (value "0R")
      (footprint "RC0402")
      (description "RES, 0 OHM, 1/16W, 1%, 0402")
      (fields (field (name "MANUFACTURER") "Yageo") (field (name "PARTNUMBER") "RC0402FR-070RL"))
      (libsource (lib "ERD TiAm") (part "RES_10K_1/16W_1%_0402"))
    )
    (comp (ref "R16")
      (value "10K")
      (footprint "RC0402")
      (description "RES, 10K OHM, 1/16W, 1%, 0402")
      (fields (field (name "MANUFACTURER") "Yageo") (field (name "PARTNUMBER") "RC0402FR-0710KL"))
      (libsource (lib "ERD TiAm") (part "RES_10K_1/16W_1%_0402"))
    )
    (comp (ref "R17")
      (value "10K")
      (footprint "RC0402")
      (description "RES, 10K OHM, 1/16W, 1%, 0402")
      (fields (field (name "MANUFACTURER") "Yageo") (field (name "PARTNUMBER") "RC0402FR-0710KL"))
      (libsource (lib "ERD TiAm") (part "RES_10K_1/16W_1%_0402"))
    )
    (comp (ref "R18")
      (value "10K")
      (footprint "RC0402")
      (description "RES, 10K OHM, 1/16W, 1%, 0402")
      (fields (field (name "MANUFACTURER") "Yageo") (field (name "PARTNUMBER") "RC0402FR-0710KL"))
      (libsource (lib "ERD TiAm") (part "RES_10K_1/16W_1%_0402"))
    )
    (comp (ref "R19")
      (value "1K")
      (footprint "RC0402")
      (description "RES, 1K OHM, 1/16W, 1%, 0402")
      (fields (field (name "MANUFACTURER") "Yageo") (field (name "PARTNUMBER") "RC0402FR-071KL"))
      (libsource (lib "ERD TiAm") (part "RES_10K_1/16W_1%_0402"))
    )
    (comp (ref "R20")
      (value "1K")
      (footprint "RC0402")
      (description "RES, 1K OHM, 1/16W, 1%, 0402")
      (fields (field (name "MANUFACTURER") "Yageo") (field (name "PARTNUMBER") "RC0402FR-071KL"))
      (libsource (lib "ERD TiAm") (part "RES_10K_1/16W_1%_0402"))
    )
    (comp (ref "R21")
      (value "1K")
      (footprint "RC0402")
      (description "RES, 1K OHM, 1/16W, 1%, 0402")
      (fields (field (name "MANUFACTURER") "Yageo") (field (name "PARTNUMBER") "RC0402FR-071KL"))
      (libsource (lib "ERD TiAm") (part "RES_10K_1/16W_1%_0402"))
    )
    (comp (ref "R22")
      (value "0.4R")
      (footprint "RC1210")
      (description "RES, 0.4 OHM, 1/2W, 1%, 2010")
      (fields (field (name "MANUFACTURER") "Yageo") (field (name "PARTNUMBER") "WSL2010R4000FEA"))
      (libsource (lib "ERD TiAm") (part "RES_10K_1/16W_1%_0402"))
    )
    (comp (ref "R23")
      (value "0.4R")
      (footprint "RC1210")
      (description "RES, 0.4 OHM, 1/2W, 1%, 2010")
      (fields (field (name "MANUFACTURER") "Yageo") (field (name "PARTNUMBER") "WSL2010R4000FEA"))
      (libsource (lib "ERD TiAm") (part "RES_10K_1/16W_1%_0402"))
    )
    (comp (ref "R24")
      (value "0.4R")
      (footprint "RC1210")
      (description "RES, 0.4 OHM, 1/2W, 1%, 2010")
      (fields (field (name "MANUFACTURER") "Yageo") (field (name "PARTNUMBER") "WSL2010R4000FEA"))
      (libsource (lib "ERD TiAm") (part "RES_10K_1/16W_1%_0402"))
    )
    (comp (ref "R25")
      (value "200K")
      (footprint "RC0402")
      (description "RES, 200K OHM, 1/16W, 1%, 0402")
      (fields (field (name "MANUFACTURER") "Yageo") (field (name "PARTNUMBER") "RC0402FR-07200KL"))
      (libsource (lib "ERD TiAm") (part "RES_10K_1/16W_1%_0402"))
    )
    (comp (ref "R26")
      (value "82K")
      (footprint "RC0402")
      (description "RES, 82K OHM, 1/16W, 1%, 0402")
      (fields (field (name "MANUFACTURER") "Yageo") (field (name "PARTNUMBER") "RC0402FR-0782KL"))
      (libsource (lib "ERD TiAm") (part "RES_10K_1/16W_1%_0402"))
    )
    (comp (ref "R27")
      (value "0R")
      (footprint "RC0402")
      (description "RES, 0 OHM, 1/16W, 1%, 0402")
      (fields (field (name "MANUFACTURER") "Yageo") (field (name "PARTNUMBER") "RC0402FR-070RL"))
      (libsource (lib "ERD TiAm") (part "RES_10K_1/16W_1%_0402"))
    )
    (comp (ref "R28")
      (value "200K")
      (footprint "RC0402")
      (description "RES, 200K OHM, 1/16W, 1%, 0402")
      (fields (field (name "MANUFACTURER") "Yageo") (field (name "PARTNUMBER") "RC0402FR-07200KL"))
      (libsource (lib "ERD TiAm") (part "RES_10K_1/16W_1%_0402"))
    )
    (comp (ref "R29")
      (value "82K")
      (footprint "RC0402")
      (description "RES, 82K OHM, 1/16W, 1%, 0402")
      (fields (field (name "MANUFACTURER") "Yageo") (field (name "PARTNUMBER") "RC0402FR-0782KL"))
      (libsource (lib "ERD TiAm") (part "RES_10K_1/16W_1%_0402"))
    )
    (comp (ref "R30")
      (value "0R")
      (footprint "RC0402")
      (description "RES, 0 OHM, 1/16W, 1%, 0402")
      (fields (field (name "MANUFACTURER") "Yageo") (field (name "PARTNUMBER") "RC0402FR-070RL"))
      (libsource (lib "ERD TiAm") (part "RES_10K_1/16W_1%_0402"))
    )
    (comp (ref "R31")
      (value "200K")
      (footprint "RC0402")
      (description "RES, 200K OHM, 1/16W, 1%, 0402")
      (fields (field (name "MANUFACTURER") "Yageo") (field (name "PARTNUMBER") "RC0402FR-07200KL"))
      (libsource (lib "ERD TiAm") (part "RES_10K_1/16W_1%_0402"))
    )
    (comp (ref "R32")
      (value "82K")
      (footprint "RC0402")
      (description "RES, 82K OHM, 1/16W, 1%, 0402")
      (fields (field (name "MANUFACTURER") "Yageo") (field (name "PARTNUMBER") "RC0402FR-0782KL"))
      (libsource (lib "ERD TiAm") (part "RES_10K_1/16W_1%_0402"))
    )
    (comp (ref "R33")
      (value "0R")
      (footprint "RC0402")
      (description "RES, 0 OHM, 1/16W, 1%, 0402")
      (fields (field (name "MANUFACTURER") "Yageo") (field (name "PARTNUMBER") "RC0402FR-070RL"))
      (libsource (lib "ERD TiAm") (part "RES_10K_1/16W_1%_0402"))
    )
    (comp (ref "R34")
      (value "0.4R")
      (footprint "RC1210")
      (description "RES, 0.4 OHM, 1/2W, 1%, 2010")
      (fields (field (name "MANUFACTURER") "Yageo") (field (name "PARTNUMBER") "WSL2010R4000FEA"))
      (libsource (lib "ERD TiAm") (part "RES_10K_1/16W_1%_0402"))
    )
    (comp (ref "R35")
      (value "0R")
      (footprint "RC0603")
      (description "RES, 0 OHM, 1/10W, 50mOhm (5%), 0603")
      (fields (field (name "MANUFACTURER") "Yageo") (field (name "PARTNUMBER") "RC0603JR-070RP"))
      (libsource (lib "ERD TiAm") (part "RES_10K_1/16W_1%_0402"))
    )
    (comp (ref "R36")
      (value "0R")
      (footprint "RC0603")
      (description "RES, 0 OHM, 1/10W, 50mOhm (5%), 0603")
      (fields (field (name "MANUFACTURER") "Yageo") (field (name "PARTNUMBER") "RC0603JR-070RP"))
      (libsource (lib "ERD TiAm") (part "RES_10K_1/16W_1%_0402"))
    )
    (comp (ref "R37")
      (value "0R")
      (footprint "RC0603")
      (description "RES, 0 OHM, 1/10W, 50mOhm (5%), 0603")
      (fields (field (name "MANUFACTURER") "Yageo") (field (name "PARTNUMBER") "RC0603JR-070RP"))
      (libsource (lib "ERD TiAm") (part "RES_10K_1/16W_1%_0402"))
    )
    (comp (ref "R38")
      (value "3R3")
      (footprint "RC0402")
      (description "RES, 3.3 OHM, 1/16W, 1%, 0402")
      (fields (field (name "MANUFACTURER") "Yageo") (field (name "PARTNUMBER") "RC0402FR-073R3L"))
      (libsource (lib "ERD TiAm") (part "RES_10K_1/16W_1%_0402"))
    )
    (comp (ref "R39")
      (value "3R3")
      (footprint "RC0402")
      (description "RES, 3.3 OHM, 1/16W, 1%, 0402")
      (fields (field (name "MANUFACTURER") "Yageo") (field (name "PARTNUMBER") "RC0402FR-073R3L"))
      (libsource (lib "ERD TiAm") (part "RES_10K_1/16W_1%_0402"))
    )
    (comp (ref "R40")
      (value "0R")
      (footprint "RC0603")
      (description "RES, 0 OHM, 1/10W, 50mOhm (5%), 0603")
      (fields (field (name "MANUFACTURER") "Yageo") (field (name "PARTNUMBER") "RC0603JR-070RP"))
      (libsource (lib "ERD TiAm") (part "RES_10K_1/16W_1%_0402"))
    )
    (comp (ref "R41")
      (value "0R")
      (footprint "RC0402")
      (description "RES, 0 OHM, 1/16W, 1%, 0402")
      (fields (field (name "MANUFACTURER") "Yageo") (field (name "PARTNUMBER") "RC0402FR-070RL"))
      (libsource (lib "ERD TiAm") (part "RES_10K_1/16W_1%_0402"))
    )
    (comp (ref "R42")
      (value "3R3")
      (footprint "RC0402")
      (description "RES, 3.3 OHM, 1/16W, 1%, 0402")
      (fields (field (name "MANUFACTURER") "Yageo") (field (name "PARTNUMBER") "RC0402FR-073R3L"))
      (libsource (lib "ERD TiAm") (part "RES_10K_1/16W_1%_0402"))
    )
    (comp (ref "R43")
      (value "3R3")
      (footprint "RC0402")
      (description "RES, 3.3 OHM, 1/16W, 1%, 0402")
      (fields (field (name "MANUFACTURER") "Yageo") (field (name "PARTNUMBER") "RC0402FR-073R3L"))
      (libsource (lib "ERD TiAm") (part "RES_10K_1/16W_1%_0402"))
    )
    (comp (ref "R44")
      (value "16K2")
      (footprint "RC0402")
      (description "RES, 16K2 OHM, 1/16W, 1%, 0402")
      (fields (field (name "MANUFACTURER") "Yageo") (field (name "PARTNUMBER") "RC0402FR-0716K2L"))
      (libsource (lib "ERD TiAm") (part "RES_10K_1/16W_1%_0402"))
    )
    (comp (ref "R45")
      (value "100K")
      (footprint "RC0402")
      (description "RES, 100K OHM, 1/16W, 1%, 0402")
      (fields (field (name "MANUFACTURER") "Yageo") (field (name "PARTNUMBER") "RC0402FR-07100KL"))
      (libsource (lib "ERD TiAm") (part "RES_10K_1/16W_1%_0402"))
    )
    (comp (ref "R46")
      (value "DNF")
      (footprint "RC0402")
      (description "RES, 0 OHM, 1/16W, 1%, 0402")
      (fields (field (name "MANUFACTURER") "Yageo") (field (name "PARTNUMBER") "RC0402FR-070RL"))
      (libsource (lib "ERD TiAm") (part "RES_10K_1/16W_1%_0402"))
    )
    (comp (ref "R47")
      (value "DNF")
      (footprint "RC0402")
      (description "RES, 0 OHM, 1/16W, 1%, 0402")
      (fields (field (name "MANUFACTURER") "Yageo") (field (name "PARTNUMBER") "RC0402FR-070RL"))
      (libsource (lib "ERD TiAm") (part "RES_10K_1/16W_1%_0402"))
    )
    (comp (ref "R48")
      (value "1K")
      (footprint "RC0402")
      (description "RES, 1K OHM, 1/16W, 1%, 0402")
      (fields (field (name "MANUFACTURER") "Yageo") (field (name "PARTNUMBER") "RC0402FR-071KL"))
      (libsource (lib "ERD TiAm") (part "RES_10K_1/16W_1%_0402"))
    )
    (comp (ref "R49")
      (value "DNF")
      (footprint "RC0402")
      (description "RES, 0 OHM, 1/16W, 1%, 0402")
      (fields (field (name "MANUFACTURER") "Yageo") (field (name "PARTNUMBER") "RC0402FR-070RL"))
      (libsource (lib "ERD TiAm") (part "RES_10K_1/16W_1%_0402"))
    )
    (comp (ref "R50")
      (value "0R")
      (footprint "RC0603")
      (description "RES, 0 OHM, 1/10W, 50mOhm (5%), 0603")
      (fields (field (name "MANUFACTURER") "Yageo") (field (name "PARTNUMBER") "RC0603JR-070RP"))
      (libsource (lib "ERD TiAm") (part "RES_10K_1/16W_1%_0402"))
    )
    (comp (ref "R51")
      (value "0R")
      (footprint "RC0603")
      (description "RES, 0 OHM, 1/10W, 50mOhm (5%), 0603")
      (fields (field (name "MANUFACTURER") "Yageo") (field (name "PARTNUMBER") "RC0603JR-070RP"))
      (libsource (lib "ERD TiAm") (part "RES_10K_1/16W_1%_0402"))
    )
    (comp (ref "R52")
      (value "1K")
      (footprint "RC0402")
      (description "RES, 1K OHM, 1/16W, 1%, 0402")
      (fields (field (name "MANUFACTURER") "Yageo") (field (name "PARTNUMBER") "RC0402FR-071KL"))
      (libsource (lib "ERD TiAm") (part "RES_10K_1/16W_1%_0402"))
    )
    (comp (ref "R53")
      (value "1K")
      (footprint "RC0402")
      (description "RES, 1K OHM, 1/16W, 1%, 0402")
      (fields (field (name "MANUFACTURER") "Yageo") (field (name "PARTNUMBER") "RC0402FR-071KL"))
      (libsource (lib "ERD TiAm") (part "RES_10K_1/16W_1%_0402"))
    )
    (comp (ref "R54")
      (value "1K")
      (footprint "RC0402")
      (description "RES, 1K OHM, 1/16W, 1%, 0402")
      (fields (field (name "MANUFACTURER") "Yageo") (field (name "PARTNUMBER") "RC0402FR-071KL"))
      (libsource (lib "ERD TiAm") (part "RES_10K_1/16W_1%_0402"))
    )
    (comp (ref "R55")
      (value "1R")
      (footprint "RC0402")
      (description "RES, 1 OHM, 1/10W, 1%, 0603")
      (fields (field (name "MANUFACTURER") "Yageo") (field (name "PARTNUMBER") "RC0603FR-071RL"))
      (libsource (lib "ERD TiAm") (part "RES_10K_1/16W_1%_0402"))
    )
    (comp (ref "R56")
      (value "0.4R")
      (footprint "RC1210")
      (description "RES, 0.4 OHM, 1/2W, 1%, 2010")
      (fields (field (name "MANUFACTURER") "Yageo") (field (name "PARTNUMBER") "WSL2010R4000FEA"))
      (libsource (lib "ERD TiAm") (part "RES_10K_1/16W_1%_0402"))
    )
    (comp (ref "R57")
      (value "0R")
      (footprint "RC0603")
      (description "RES, 0 OHM, 1/10W, 50mOhm (5%), 0603")
      (fields (field (name "MANUFACTURER") "Yageo") (field (name "PARTNUMBER") "RC0603JR-070RP"))
      (libsource (lib "ERD TiAm") (part "RES_10K_1/16W_1%_0402"))
    )
    (comp (ref "R58")
      (value "0R")
      (footprint "RC0603")
      (description "RES, 0 OHM, 1/10W, 50mOhm (5%), 0603")
      (fields (field (name "MANUFACTURER") "Yageo") (field (name "PARTNUMBER") "RC0603JR-070RP"))
      (libsource (lib "ERD TiAm") (part "RES_10K_1/16W_1%_0402"))
    )
    (comp (ref "R59")
      (value "0R")
      (footprint "RC0402")
      (description "RES, 0 OHM, 1/16W, 1%, 0402")
      (fields (field (name "MANUFACTURER") "Yageo") (field (name "PARTNUMBER") "RC0402FR-070RL"))
      (libsource (lib "ERD TiAm") (part "RES_10K_1/16W_1%_0402"))
    )
    (comp (ref "R60")
      (value "16K2")
      (footprint "RC0402")
      (description "RES, 16K2 OHM, 1/16W, 1%, 0402")
      (fields (field (name "MANUFACTURER") "Yageo") (field (name "PARTNUMBER") "RC0402FR-0716K2L"))
      (libsource (lib "ERD TiAm") (part "RES_10K_1/16W_1%_0402"))
    )
    (comp (ref "R61")
      (value "100K")
      (footprint "RC0402")
      (description "RES, 100K OHM, 1/16W, 1%, 0402")
      (fields (field (name "MANUFACTURER") "Yageo") (field (name "PARTNUMBER") "RC0402FR-07100KL"))
      (libsource (lib "ERD TiAm") (part "RES_10K_1/16W_1%_0402"))
    )
    (comp (ref "R62")
      (value "1K")
      (footprint "RC0402")
      (description "RES, 1K OHM, 1/16W, 1%, 0402")
      (fields (field (name "MANUFACTURER") "Yageo") (field (name "PARTNUMBER") "RC0402FR-071KL"))
      (libsource (lib "ERD TiAm") (part "RES_10K_1/16W_1%_0402"))
    )
    (comp (ref "R63")
      (value "DNF")
      (footprint "RC0402")
      (description "RES, 0 OHM, 1/16W, 1%, 0402")
      (fields (field (name "MANUFACTURER") "Yageo") (field (name "PARTNUMBER") "RC0402FR-070RL"))
      (libsource (lib "ERD TiAm") (part "RES_10K_1/16W_1%_0402"))
    )
    (comp (ref "R64")
      (value "1K")
      (footprint "RC0402")
      (description "RES, 1K OHM, 1/16W, 1%, 0402")
      (fields (field (name "MANUFACTURER") "Yageo") (field (name "PARTNUMBER") "RC0402FR-071KL"))
      (libsource (lib "ERD TiAm") (part "RES_10K_1/16W_1%_0402"))
    )
    (comp (ref "R65")
      (value "1R")
      (footprint "RC0402")
      (description "RES, 1 OHM, 1/10W, 1%, 0603")
      (fields (field (name "MANUFACTURER") "Yageo") (field (name "PARTNUMBER") "RC0603FR-071RL"))
      (libsource (lib "ERD TiAm") (part "RES_10K_1/16W_1%_0402"))
    )
    (comp (ref "S1")
      (value "2118729-4")
      (footprint "2118727-2")
      (description "RF Shield, 31.1mm x 44.6mm x 2mm")
      (libsource (lib "ERD TiAm") (part "BMI-S-206-F"))
    )
    (comp (ref "U1")
      (value "DRV110APWR")
      (footprint "TSSOP-14")
      (description "GATE DRIVE, TSSOP-14")
      (libsource (lib "ERD TiAm") (part "DRV110"))
    )
    (comp (ref "U2")
      (value "DRV110APWR")
      (footprint "TSSOP-14")
      (description "GATE DRIVE, TSSOP-14")
      (libsource (lib "ERD TiAm") (part "DRV110"))
    )
    (comp (ref "U3")
      (value "DRV110APWR")
      (footprint "TSSOP-14")
      (description "GATE DRIVE, TSSOP-14")
      (libsource (lib "ERD TiAm") (part "DRV110"))
    )
    (comp (ref "U4")
      (value "INA223")
      (description "Power Monitor, I2C, SON-10")
      (libsource (lib "ERD TiAm") (part "INA223"))
    )
    (comp (ref "U5")
      (value "AD823A")
      (footprint "SOIC-8")
      (description "Op-AMP, Dual, 17MHz, SOIC-8")
      (libsource (lib "") (part "AD823A_1"))
    )
    (comp (ref "U6")
      (value "DRV2510-Q1")
      (footprint "HTSSOP-16")
      (description "Haptic Driver, 3A, HTSSOP-16")
      (libsource (lib "ERD TiAm") (part "DRV2510-Q1"))
    )
    (comp (ref "U7")
      (value "DRV2510-Q1")
      (footprint "HTSSOP-16")
      (description "Haptic Driver, 3A, HTSSOP-16")
      (libsource (lib "ERD TiAm") (part "DRV2510-Q1"))
    )
    (comp (ref "U8")
      (value "EMIF08-1005M16")
      (footprint "QFN-16L")
      (description "EMI Filter, ESD, QFN-16L")
      (libsource (lib "ERD TiAm") (part "EMIF08-1005M16"))
    )
    (comp (ref "U9")
      (value "EMIF08-1005M16")
      (footprint "QFN-16L")
      (description "EMI Filter, ESD, QFN-16L")
      (libsource (lib "ERD TiAm") (part "EMIF08-1005M16"))
    )
    (comp (ref "U10")
      (value "EMIF08-1005M16")
      (footprint "QFN-16L")
      (description "EMI Filter, ESD, QFN-16L")
      (libsource (lib "ERD TiAm") (part "EMIF08-1005M16"))
    )
    (comp (ref "U11")
      (value "INA223")
      (description "Power Monitor, I2C, SON-10")
      (libsource (lib "ERD TiAm") (part "INA223"))
    )
    (comp (ref "U12")
      (value "AD823A")
      (footprint "SOIC-8")
      (description "Op-AMP, Dual, 17MHz, SOIC-8")
      (libsource (lib "") (part "AD823A_1"))
    )
  )
  (nets
    (net (code "1") (name "/ADC_1") (class "Default")
      (node (ref "P1") (pin "26") (pinfunction "26_26") (pintype "passive"))
      (node (ref "U9") (pin "9") (pinfunction "9_9") (pintype "passive"))
    )
    (net (code "2") (name "/ADC_2") (class "Default")
      (node (ref "P1") (pin "28") (pinfunction "28_28") (pintype "passive"))
      (node (ref "U10") (pin "11") (pinfunction "11_11") (pintype "passive"))
    )
    (net (code "3") (name "/DAC1") (class "Default")
      (node (ref "R41") (pin "2") (pinfunction "2_2") (pintype "passive"))
      (node (ref "R46") (pin "2") (pinfunction "2_2") (pintype "passive"))
      (node (ref "U8") (pin "8") (pinfunction "8_8") (pintype "passive"))
    )
    (net (code "4") (name "/DAC2") (class "Default")
      (node (ref "R47") (pin "2") (pinfunction "2_2") (pintype "passive"))
      (node (ref "R59") (pin "2") (pinfunction "2_2") (pintype "passive"))
      (node (ref "U9") (pin "5") (pinfunction "5_5") (pintype "passive"))
    )
    (net (code "5") (name "/DAC_1") (class "Default")
      (node (ref "P1") (pin "17") (pinfunction "17_17") (pintype "passive"))
      (node (ref "U8") (pin "9") (pinfunction "9_9") (pintype "passive"))
    )
    (net (code "6") (name "/DAC_2") (class "Default")
      (node (ref "P1") (pin "27") (pinfunction "27_27") (pintype "passive"))
      (node (ref "U9") (pin "12") (pinfunction "12_12") (pintype "passive"))
    )
    (net (code "7") (name "/EN1") (class "Default")
      (node (ref "U1") (pin "13") (pinfunction "EN_13") (pintype "passive"))
      (node (ref "U8") (pin "1") (pinfunction "1_1") (pintype "passive"))
    )
    (net (code "8") (name "/EN2") (class "Default")
      (node (ref "U2") (pin "13") (pinfunction "EN_13") (pintype "passive"))
      (node (ref "U8") (pin "2") (pinfunction "2_2") (pintype "passive"))
    )
    (net (code "9") (name "/EN3") (class "Default")
      (node (ref "U3") (pin "13") (pinfunction "EN_13") (pintype "passive"))
      (node (ref "U8") (pin "3") (pinfunction "3_3") (pintype "passive"))
    )
    (net (code "10") (name "/GPIO_1") (class "Default")
      (node (ref "P1") (pin "3") (pinfunction "3_3") (pintype "passive"))
      (node (ref "U8") (pin "16") (pinfunction "16_16") (pintype "passive"))
    )
    (net (code "11") (name "/GPIO_2") (class "Default")
      (node (ref "P1") (pin "5") (pinfunction "5_5") (pintype "passive"))
      (node (ref "U8") (pin "15") (pinfunction "15_15") (pintype "passive"))
    )
    (net (code "12") (name "/GPIO_3") (class "Default")
      (node (ref "P1") (pin "7") (pinfunction "7_7") (pintype "passive"))
      (node (ref "U8") (pin "14") (pinfunction "14_14") (pintype "passive"))
    )
    (net (code "13") (name "/GPIO_4") (class "Default")
      (node (ref "P1") (pin "9") (pinfunction "9_9") (pintype "passive"))
      (node (ref "U8") (pin "13") (pinfunction "13_13") (pintype "passive"))
    )
    (net (code "14") (name "/GPIO_5") (class "Default")
      (node (ref "P1") (pin "15") (pinfunction "15_15") (pintype "passive"))
      (node (ref "U8") (pin "10") (pinfunction "10_10") (pintype "passive"))
    )
    (net (code "15") (name "/GPIO_6") (class "Default")
      (node (ref "P1") (pin "19") (pinfunction "19_19") (pintype "passive"))
      (node (ref "U9") (pin "16") (pinfunction "16_16") (pintype "passive"))
    )
    (net (code "16") (name "/GPIO_7") (class "Default")
      (node (ref "P1") (pin "25") (pinfunction "25_25") (pintype "passive"))
      (node (ref "U9") (pin "13") (pinfunction "13_13") (pintype "passive"))
    )
    (net (code "17") (name "/GPIO_8") (class "Default")
      (node (ref "P1") (pin "4") (pinfunction "4_4") (pintype "passive"))
      (node (ref "U9") (pin "11") (pinfunction "11_11") (pintype "passive"))
    )
    (net (code "18") (name "/GPIO_9") (class "Default")
      (node (ref "P1") (pin "6") (pinfunction "6_6") (pintype "passive"))
      (node (ref "U9") (pin "10") (pinfunction "10_10") (pintype "passive"))
    )
    (net (code "19") (name "/GPIO_10") (class "Default")
      (node (ref "P1") (pin "8") (pinfunction "8_8") (pintype "passive"))
      (node (ref "U10") (pin "16") (pinfunction "16_16") (pintype "passive"))
    )
    (net (code "20") (name "/GPIO_11") (class "Default")
      (node (ref "P1") (pin "12") (pinfunction "12_12") (pintype "passive"))
      (node (ref "U10") (pin "15") (pinfunction "15_15") (pintype "passive"))
    )
    (net (code "21") (name "/GPIO_12") (class "Default")
      (node (ref "P1") (pin "14") (pinfunction "14_14") (pintype "passive"))
      (node (ref "U10") (pin "14") (pinfunction "14_14") (pintype "passive"))
    )
    (net (code "22") (name "/GPIO_13") (class "Default")
      (node (ref "P1") (pin "16") (pinfunction "16_16") (pintype "passive"))
      (node (ref "U10") (pin "13") (pinfunction "13_13") (pintype "passive"))
    )
    (net (code "23") (name "/GPIO_14") (class "Default")
      (node (ref "P1") (pin "24") (pinfunction "24_24") (pintype "passive"))
      (node (ref "U10") (pin "12") (pinfunction "12_12") (pintype "passive"))
    )
    (net (code "24") (name "/GPIO_17") (class "Default")
      (node (ref "P2") (pin "1") (pinfunction "1_1") (pintype "passive+no_connect"))
    )
    (net (code "25") (name "/GPIO_18") (class "Default")
      (node (ref "P2") (pin "3") (pinfunction "3_3") (pintype "passive+no_connect"))
    )
    (net (code "26") (name "/GPIO_19") (class "Default")
      (node (ref "P2") (pin "5") (pinfunction "5_5") (pintype "passive+no_connect"))
    )
    (net (code "27") (name "/GPIO_20") (class "Default")
      (node (ref "P2") (pin "7") (pinfunction "7_7") (pintype "passive+no_connect"))
    )
    (net (code "28") (name "/GPIO_21") (class "Default")
      (node (ref "P2") (pin "9") (pinfunction "9_9") (pintype "passive+no_connect"))
    )
    (net (code "29") (name "/I2C1_SCL") (class "Default")
      (node (ref "U11") (pin "6") (pinfunction "SCL_6") (pintype "passive"))
      (node (ref "U4") (pin "6") (pinfunction "SCL_6") (pintype "passive"))
      (node (ref "U6") (pin "5") (pinfunction "SCL_5") (pintype "passive"))
      (node (ref "U8") (pin "6") (pinfunction "6_6") (pintype "passive"))
    )
    (net (code "30") (name "/I2C1_SDA") (class "Default")
      (node (ref "U11") (pin "7") (pinfunction "SDA_7") (pintype "passive"))
      (node (ref "U4") (pin "7") (pinfunction "SDA_7") (pintype "passive"))
      (node (ref "U6") (pin "4") (pinfunction "SDA_4") (pintype "passive"))
      (node (ref "U8") (pin "5") (pinfunction "5_5") (pintype "passive"))
    )
    (net (code "31") (name "/I2C2_SCL") (class "Default")
      (node (ref "U7") (pin "5") (pinfunction "SCL_5") (pintype "passive"))
      (node (ref "U9") (pin "3") (pinfunction "3_3") (pintype "passive"))
    )
    (net (code "32") (name "/I2C2_SDA") (class "Default")
      (node (ref "U7") (pin "4") (pinfunction "SDA_4") (pintype "passive"))
      (node (ref "U9") (pin "2") (pinfunction "2_2") (pintype "passive"))
    )
    (net (code "33") (name "/I2C_SCL_1") (class "Default")
      (node (ref "P1") (pin "13") (pinfunction "13_13") (pintype "passive"))
      (node (ref "U8") (pin "11") (pinfunction "11_11") (pintype "passive"))
    )
    (net (code "34") (name "/I2C_SCL_2") (class "Default")
      (node (ref "P1") (pin "23") (pinfunction "23_23") (pintype "passive"))
      (node (ref "U9") (pin "14") (pinfunction "14_14") (pintype "passive"))
    )
    (net (code "35") (name "/I2C_SDA_1") (class "Default")
      (node (ref "P1") (pin "11") (pinfunction "11_11") (pintype "passive"))
      (node (ref "U8") (pin "12") (pinfunction "12_12") (pintype "passive"))
    )
    (net (code "36") (name "/I2C_SDA_2") (class "Default")
      (node (ref "P1") (pin "21") (pinfunction "21_21") (pintype "passive"))
      (node (ref "U9") (pin "15") (pinfunction "15_15") (pintype "passive"))
    )
    (net (code "37") (name "/PWM1") (class "Default")
      (node (ref "R49") (pin "2") (pinfunction "2_2") (pintype "passive"))
      (node (ref "R53") (pin "1") (pinfunction "1_1") (pintype "passive"))
      (node (ref "U8") (pin "7") (pinfunction "7_7") (pintype "passive"))
    )
    (net (code "38") (name "/PWM2") (class "Default")
      (node (ref "R54") (pin "1") (pinfunction "1_1") (pintype "passive"))
      (node (ref "R63") (pin "2") (pinfunction "2_2") (pintype "passive"))
      (node (ref "U9") (pin "4") (pinfunction "4_4") (pintype "passive"))
    )
    (net (code "39") (name "/SOLENOID1_N") (class "Default")
      (node (ref "C13") (pin "1") (pinfunction "1_1") (pintype "passive"))
      (node (ref "P2") (pin "4") (pinfunction "4_4") (pintype "passive"))
      (node (ref "R8") (pin "1") (pinfunction "1_1") (pintype "passive"))
    )
    (net (code "40") (name "/SOLENOID1_P") (class "Default")
      (node (ref "C1") (pin "1") (pinfunction "1_1") (pintype "passive"))
      (node (ref "P2") (pin "2") (pinfunction "2_2") (pintype "passive"))
      (node (ref "R2") (pin "1") (pinfunction "1_1") (pintype "passive"))
    )
    (net (code "41") (name "/SOLENOID2_N") (class "Default")
      (node (ref "C14") (pin "1") (pinfunction "1_1") (pintype "passive"))
      (node (ref "P2") (pin "8") (pinfunction "8_8") (pintype "passive"))
      (node (ref "R10") (pin "1") (pinfunction "1_1") (pintype "passive"))
    )
    (net (code "42") (name "/SOLENOID2_P") (class "Default")
      (node (ref "C2") (pin "1") (pinfunction "1_1") (pintype "passive"))
      (node (ref "P2") (pin "6") (pinfunction "6_6") (pintype "passive"))
      (node (ref "R4") (pin "1") (pinfunction "1_1") (pintype "passive"))
    )
    (net (code "43") (name "/SOLENOID3_N") (class "Default")
      (node (ref "C15") (pin "1") (pinfunction "1_1") (pintype "passive"))
      (node (ref "P2") (pin "12") (pinfunction "12_12") (pintype "passive"))
      (node (ref "R12") (pin "1") (pinfunction "1_1") (pintype "passive"))
    )
    (net (code "44") (name "/SOLENOID3_P") (class "Default")
      (node (ref "C3") (pin "1") (pinfunction "1_1") (pintype "passive"))
      (node (ref "P2") (pin "10") (pinfunction "10_10") (pintype "passive"))
      (node (ref "R6") (pin "1") (pinfunction "1_1") (pintype "passive"))
    )
    (net (code "45") (name "/STATUS1") (class "Default")
      (node (ref "R16") (pin "1") (pinfunction "1_1") (pintype "passive"))
      (node (ref "U1") (pin "12") (pinfunction "STATUS_12") (pintype "passive"))
      (node (ref "U10") (pin "1") (pinfunction "1_1") (pintype "passive"))
    )
    (net (code "46") (name "/STATUS2") (class "Default")
      (node (ref "R17") (pin "1") (pinfunction "1_1") (pintype "passive"))
      (node (ref "U10") (pin "2") (pinfunction "2_2") (pintype "passive"))
      (node (ref "U2") (pin "12") (pinfunction "STATUS_12") (pintype "passive"))
    )
    (net (code "47") (name "/STATUS3") (class "Default")
      (node (ref "R18") (pin "1") (pinfunction "1_1") (pintype "passive"))
      (node (ref "U10") (pin "3") (pinfunction "3_3") (pintype "passive"))
      (node (ref "U3") (pin "12") (pinfunction "STATUS_12") (pintype "passive"))
    )
    (net (code "48") (name "/VSO1A_N") (class "Default")
      (node (ref "C45") (pin "1") (pinfunction "1_1") (pintype "passive"))
      (node (ref "P2") (pin "16") (pinfunction "16_16") (pintype "passive"))
      (node (ref "R50") (pin "1") (pinfunction "1_1") (pintype "passive"))
    )
    (net (code "49") (name "/VSO1A_P") (class "Default")
      (node (ref "C34") (pin "1") (pinfunction "1_1") (pintype "passive"))
      (node (ref "P2") (pin "14") (pinfunction "14_14") (pintype "passive"))
      (node (ref "R35") (pin "1") (pinfunction "1_1") (pintype "passive"))
    )
    (net (code "50") (name "/VSO1B_N") (class "Default")
      (node (ref "C39") (pin "1") (pinfunction "1_1") (pintype "passive"))
      (node (ref "P2") (pin "24") (pinfunction "24_24") (pintype "passive"))
      (node (ref "R40") (pin "1") (pinfunction "1_1") (pintype "passive"))
    )
    (net (code "51") (name "/VSO1B_P") (class "Default")
      (node (ref "C26") (pin "1") (pinfunction "1_1") (pintype "passive"))
      (node (ref "P2") (pin "22") (pinfunction "22_22") (pintype "passive"))
      (node (ref "R37") (pin "1") (pinfunction "1_1") (pintype "passive"))
    )
    (net (code "52") (name "/VSO1_ADC") (class "Default")
      (node (ref "U10") (pin "6") (pinfunction "6_6") (pintype "passive"))
      (node (ref "U11") (pin "5") (pinfunction "VOUT_5") (pintype "passive"))
      (node (ref "U4") (pin "5") (pinfunction "VOUT_5") (pintype "passive"))
    )
    (net (code "53") (name "/VSO1_EN") (class "Default")
      (node (ref "U6") (pin "2") (pinfunction "EN_2") (pintype "passive"))
      (node (ref "U8") (pin "4") (pinfunction "4_4") (pintype "passive"))
    )
    (net (code "54") (name "/VSO1_INT") (class "Default")
      (node (ref "U10") (pin "4") (pinfunction "4_4") (pintype "passive"))
      (node (ref "U6") (pin "14") (pinfunction "INTZ_14") (pintype "passive"))
    )
    (net (code "55") (name "/VSO1_STBY") (class "Default")
      (node (ref "U10") (pin "5") (pinfunction "5_5") (pintype "passive"))
      (node (ref "U6") (pin "8") (pinfunction "STBY_8") (pintype "passive"))
    )
    (net (code "56") (name "/VSO2A_N") (class "Default")
      (node (ref "C46") (pin "1") (pinfunction "1_1") (pintype "passive"))
      (node (ref "P2") (pin "20") (pinfunction "20_20") (pintype "passive"))
      (node (ref "R51") (pin "1") (pinfunction "1_1") (pintype "passive"))
    )
    (net (code "57") (name "/VSO2A_P") (class "Default")
      (node (ref "C36") (pin "1") (pinfunction "1_1") (pintype "passive"))
      (node (ref "P2") (pin "18") (pinfunction "18_18") (pintype "passive"))
      (node (ref "R36") (pin "1") (pinfunction "1_1") (pintype "passive"))
    )
    (net (code "58") (name "/VSO2B_N") (class "Default")
      (node (ref "C56") (pin "1") (pinfunction "1_1") (pintype "passive"))
      (node (ref "P2") (pin "28") (pinfunction "28_28") (pintype "passive"))
      (node (ref "R58") (pin "1") (pinfunction "1_1") (pintype "passive"))
    )
    (net (code "59") (name "/VSO2B_P") (class "Default")
      (node (ref "C55") (pin "1") (pinfunction "1_1") (pintype "passive"))
      (node (ref "P2") (pin "26") (pinfunction "26_26") (pintype "passive"))
      (node (ref "R57") (pin "1") (pinfunction "1_1") (pintype "passive"))
    )
    (net (code "60") (name "/VSO2_ADC") (class "Default")
      (node (ref "U9") (pin "8") (pinfunction "8_8") (pintype "passive"))
    )
    (net (code "61") (name "/VSO2_EN") (class "Default")
      (node (ref "U7") (pin "2") (pinfunction "EN_2") (pintype "passive"))
      (node (ref "U9") (pin "1") (pinfunction "1_1") (pintype "passive"))
    )
    (net (code "62") (name "/VSO2_INT") (class "Default")
      (node (ref "U7") (pin "14") (pinfunction "INTZ_14") (pintype "passive"))
      (node (ref "U9") (pin "6") (pinfunction "6_6") (pintype "passive"))
    )
    (net (code "63") (name "/VSO2_STBY") (class "Default")
      (node (ref "U7") (pin "8") (pinfunction "STBY_8") (pintype "passive"))
      (node (ref "U9") (pin "7") (pinfunction "7_7") (pintype "passive"))
    )
    (net (code "64") (name "12V0A") (class "Default")
      (node (ref "C4") (pin "2") (pinfunction "2_2") (pintype "passive"))
      (node (ref "C7") (pin "2") (pinfunction "2_2") (pintype "passive"))
      (node (ref "P2") (pin "11") (pinfunction "11_11") (pintype "passive"))
      (node (ref "R1") (pin "2") (pinfunction "2_2") (pintype "passive"))
      (node (ref "R7") (pin "2") (pinfunction "2_2") (pintype "passive"))
    )
    (net (code "65") (name "12V0B") (class "Default")
      (node (ref "C5") (pin "2") (pinfunction "2_2") (pintype "passive"))
      (node (ref "C9") (pin "2") (pinfunction "2_2") (pintype "passive"))
      (node (ref "P2") (pin "15") (pinfunction "15_15") (pintype "passive"))
      (node (ref "R3") (pin "2") (pinfunction "2_2") (pintype "passive"))
      (node (ref "R9") (pin "2") (pinfunction "2_2") (pintype "passive"))
    )
    (net (code "66") (name "12V0C") (class "Default")
      (node (ref "C11") (pin "2") (pinfunction "2_2") (pintype "passive"))
      (node (ref "C6") (pin "2") (pinfunction "2_2") (pintype "passive"))
      (node (ref "P2") (pin "19") (pinfunction "19_19") (pintype "passive"))
      (node (ref "R11") (pin "2") (pinfunction "2_2") (pintype "passive"))
      (node (ref "R5") (pin "2") (pinfunction "2_2") (pintype "passive"))
    )
    (net (code "67") (name "12V0D") (class "Default")
      (node (ref "C27") (pin "1") (pinfunction "1_1") (pintype "passive"))
      (node (ref "C28") (pin "1") (pinfunction "1_1") (pintype "passive"))
      (node (ref "C29") (pin "2") (pinfunction "2_2") (pintype "passive"))
      (node (ref "P2") (pin "23") (pinfunction "23_23") (pintype "passive"))
      (node (ref "R34") (pin "1") (pinfunction "1_1") (pintype "passive"))
      (node (ref "U4") (pin "10") (pinfunction "VIN+_10") (pintype "passive"))
      (node (ref "U4") (pin "9") (pinfunction "VIN+_9") (pintype "passive"))
      (node (ref "U6") (pin "15") (pinfunction "VDD_15") (pintype "passive"))
    )
    (net (code "68") (name "12V0E") (class "Default")
      (node (ref "C30") (pin "1") (pinfunction "1_1") (pintype "passive"))
      (node (ref "C31") (pin "1") (pinfunction "1_1") (pintype "passive"))
      (node (ref "C32") (pin "2") (pinfunction "2_2") (pintype "passive"))
      (node (ref "P2") (pin "27") (pinfunction "27_27") (pintype "passive"))
      (node (ref "R56") (pin "1") (pinfunction "1_1") (pintype "passive"))
      (node (ref "U11") (pin "10") (pinfunction "VIN+_10") (pintype "passive"))
      (node (ref "U11") (pin "9") (pinfunction "VIN+_9") (pintype "passive"))
      (node (ref "U7") (pin "15") (pinfunction "VDD_15") (pintype "passive"))
    )
    (net (code "69") (name "GND") (class "Default")
      (node (ref "C1") (pin "2") (pinfunction "2_2") (pintype "passive"))
      (node (ref "C10") (pin "1") (pinfunction "1_1") (pintype "passive"))
      (node (ref "C11") (pin "1") (pinfunction "1_1") (pintype "passive"))
      (node (ref "C12") (pin "1") (pinfunction "1_1") (pintype "passive"))
      (node (ref "C13") (pin "2") (pinfunction "2_2") (pintype "passive"))
      (node (ref "C14") (pin "2") (pinfunction "2_2") (pintype "passive"))
      (node (ref "C15") (pin "2") (pinfunction "2_2") (pintype "passive"))
      (node (ref "C16") (pin "1") (pinfunction "1_1") (pintype "passive"))
      (node (ref "C17") (pin "1") (pinfunction "1_1") (pintype "passive"))
      (node (ref "C18") (pin "1") (pinfunction "1_1") (pintype "passive"))
      (node (ref "C19") (pin "1") (pinfunction "1_1") (pintype "passive"))
      (node (ref "C2") (pin "2") (pinfunction "2_2") (pintype "passive"))
      (node (ref "C20") (pin "1") (pinfunction "1_1") (pintype "passive"))
      (node (ref "C21") (pin "1") (pinfunction "1_1") (pintype "passive"))
      (node (ref "C22") (pin "1") (pinfunction "1_1") (pintype "passive"))
      (node (ref "C25") (pin "1") (pinfunction "1_1") (pintype "passive"))
      (node (ref "C26") (pin "2") (pinfunction "2_2") (pintype "passive"))
      (node (ref "C27") (pin "2") (pinfunction "2_2") (pintype "passive"))
      (node (ref "C28") (pin "2") (pinfunction "2_2") (pintype "passive"))
      (node (ref "C29") (pin "1") (pinfunction "1_1") (pintype "passive"))
      (node (ref "C3") (pin "2") (pinfunction "2_2") (pintype "passive"))
      (node (ref "C30") (pin "2") (pinfunction "2_2") (pintype "passive"))
      (node (ref "C31") (pin "2") (pinfunction "2_2") (pintype "passive"))
      (node (ref "C32") (pin "1") (pinfunction "1_1") (pintype "passive"))
      (node (ref "C33") (pin "1") (pinfunction "1_1") (pintype "passive"))
      (node (ref "C34") (pin "2") (pinfunction "2_2") (pintype "passive"))
      (node (ref "C35") (pin "1") (pinfunction "1_1") (pintype "passive"))
      (node (ref "C36") (pin "2") (pinfunction "2_2") (pintype "passive"))
      (node (ref "C37") (pin "1") (pinfunction "1_1") (pintype "passive"))
      (node (ref "C38") (pin "1") (pinfunction "1_1") (pintype "passive"))
      (node (ref "C39") (pin "2") (pinfunction "2_2") (pintype "passive"))
      (node (ref "C4") (pin "1") (pinfunction "1_1") (pintype "passive"))
      (node (ref "C44") (pin "1") (pinfunction "1_1") (pintype "passive"))
      (node (ref "C45") (pin "2") (pinfunction "2_2") (pintype "passive"))
      (node (ref "C46") (pin "2") (pinfunction "2_2") (pintype "passive"))
      (node (ref "C47") (pin "1") (pinfunction "1_1") (pintype "passive"))
      (node (ref "C48") (pin "1") (pinfunction "1_1") (pintype "passive"))
      (node (ref "C49") (pin "1") (pintype "passive"))
      (node (ref "C5") (pin "1") (pinfunction "1_1") (pintype "passive"))
      (node (ref "C50") (pin "1") (pintype "passive"))
      (node (ref "C51") (pin "1") (pinfunction "1_1") (pintype "passive"))
      (node (ref "C52") (pin "1") (pinfunction "1_1") (pintype "passive"))
      (node (ref "C53") (pin "1") (pinfunction "1_1") (pintype "passive"))
      (node (ref "C54") (pin "1") (pinfunction "1_1") (pintype "passive"))
      (node (ref "C55") (pin "2") (pinfunction "2_2") (pintype "passive"))
      (node (ref "C56") (pin "2") (pinfunction "2_2") (pintype "passive"))
      (node (ref "C57") (pin "1") (pinfunction "1_1") (pintype "passive"))
      (node (ref "C6") (pin "1") (pinfunction "1_1") (pintype "passive"))
      (node (ref "C7") (pin "1") (pinfunction "1_1") (pintype "passive"))
      (node (ref "C8") (pin "1") (pinfunction "1_1") (pintype "passive"))
      (node (ref "C9") (pin "1") (pinfunction "1_1") (pintype "passive"))
      (node (ref "MH1") (pin "1") (pinfunction "1_1") (pintype "passive"))
      (node (ref "MH2") (pin "1") (pinfunction "1_1") (pintype "passive"))
      (node (ref "MH3") (pin "1") (pinfunction "1_1") (pintype "passive"))
      (node (ref "MH4") (pin "1") (pinfunction "1_1") (pintype "passive"))
      (node (ref "P1") (pin "1") (pinfunction "1_1") (pintype "passive"))
      (node (ref "P1") (pin "10") (pinfunction "10_10") (pintype "passive"))
      (node (ref "P1") (pin "2") (pinfunction "2_2") (pintype "passive"))
      (node (ref "P1") (pin "20") (pinfunction "20_20") (pintype "passive"))
      (node (ref "P1") (pin "29") (pinfunction "29_29") (pintype "passive"))
      (node (ref "P1") (pin "30") (pinfunction "30_30") (pintype "passive"))
      (node (ref "P2") (pin "13") (pinfunction "13_13") (pintype "passive"))
      (node (ref "P2") (pin "17") (pinfunction "17_17") (pintype "passive"))
      (node (ref "P2") (pin "21") (pinfunction "21_21") (pintype "passive"))
      (node (ref "P2") (pin "25") (pinfunction "25_25") (pintype "passive"))
      (node (ref "P2") (pin "29") (pinfunction "29_29") (pintype "passive"))
      (node (ref "P2") (pin "30") (pinfunction "30_30") (pintype "passive"))
      (node (ref "R22") (pin "2") (pinfunction "2_2") (pintype "passive"))
      (node (ref "R23") (pin "2") (pinfunction "2_2") (pintype "passive"))
      (node (ref "R24") (pin "2") (pinfunction "2_2") (pintype "passive"))
      (node (ref "R25") (pin "1") (pinfunction "1_1") (pintype "passive"))
      (node (ref "R26") (pin "1") (pinfunction "1_1") (pintype "passive"))
      (node (ref "R27") (pin "1") (pinfunction "1_1") (pintype "passive"))
      (node (ref "R28") (pin "1") (pinfunction "1_1") (pintype "passive"))
      (node (ref "R29") (pin "1") (pinfunction "1_1") (pintype "passive"))
      (node (ref "R30") (pin "1") (pinfunction "1_1") (pintype "passive"))
      (node (ref "R31") (pin "1") (pinfunction "1_1") (pintype "passive"))
      (node (ref "R32") (pin "1") (pinfunction "1_1") (pintype "passive"))
      (node (ref "R33") (pin "1") (pinfunction "1_1") (pintype "passive"))
      (node (ref "R52") (pin "2") (pinfunction "2_2") (pintype "passive"))
      (node (ref "R55") (pin "2") (pinfunction "2_2") (pintype "passive"))
      (node (ref "R64") (pin "2") (pinfunction "2_2") (pintype "passive"))
      (node (ref "R65") (pin "2") (pinfunction "2_2") (pintype "passive"))
      (node (ref "S1") (pin "1") (pinfunction "GND_1") (pintype "passive"))
      (node (ref "U1") (pin "8") (pinfunction "GND_8") (pintype "passive"))
      (node (ref "U10") (pin "10") (pinfunction "10_10") (pintype "passive"))
      (node (ref "U10") (pin "17") (pinfunction "PAD_17") (pintype "passive"))
      (node (ref "U10") (pin "9") (pinfunction "9_9") (pintype "passive"))
      (node (ref "U11") (pin "11") (pinfunction "PAD_11") (pintype "passive"))
      (node (ref "U11") (pin "3") (pinfunction "GND_3") (pintype "passive"))
      (node (ref "U11") (pin "8") (pinfunction "A0_8") (pintype "passive"))
      (node (ref "U12") (pin "4") (pinfunction "-VS_4") (pintype "passive"))
      (node (ref "U2") (pin "8") (pinfunction "GND_8") (pintype "passive"))
      (node (ref "U3") (pin "8") (pinfunction "GND_8") (pintype "passive"))
      (node (ref "U4") (pin "11") (pinfunction "PAD_11") (pintype "passive"))
      (node (ref "U4") (pin "3") (pinfunction "GND_3") (pintype "passive"))
      (node (ref "U4") (pin "8") (pinfunction "A0_8") (pintype "passive"))
      (node (ref "U5") (pin "4") (pinfunction "-VS_4") (pintype "passive"))
      (node (ref "U6") (pin "1") (pinfunction "GND_1") (pintype "passive"))
      (node (ref "U6") (pin "16") (pinfunction "GND_16") (pintype "passive"))
      (node (ref "U6") (pin "17") (pinfunction "PAD_17") (pintype "passive"))
      (node (ref "U6") (pin "9") (pinfunction "GND_9") (pintype "passive"))
      (node (ref "U7") (pin "1") (pinfunction "GND_1") (pintype "passive"))
      (node (ref "U7") (pin "16") (pinfunction "GND_16") (pintype "passive"))
      (node (ref "U7") (pin "17") (pinfunction "PAD_17") (pintype "passive"))
      (node (ref "U7") (pin "9") (pinfunction "GND_9") (pintype "passive"))
      (node (ref "U8") (pin "17") (pinfunction "PAD_17") (pintype "passive"))
      (node (ref "U9") (pin "17") (pinfunction "PAD_17") (pintype "passive"))
    )
    (net (code "70") (name "Net-(C33-Pad2)") (class "Default")
      (node (ref "C33") (pin "2") (pinfunction "2_2") (pintype "passive"))
      (node (ref "R38") (pin "1") (pinfunction "1_1") (pintype "passive"))
    )
    (net (code "71") (name "Net-(C35-Pad2)") (class "Default")
      (node (ref "C35") (pin "2") (pinfunction "2_2") (pintype "passive"))
      (node (ref "R39") (pin "1") (pinfunction "1_1") (pintype "passive"))
    )
    (net (code "72") (name "Net-(C37-Pad2)") (class "Default")
      (node (ref "C37") (pin "2") (pinfunction "2_2") (pintype "passive"))
      (node (ref "R42") (pin "1") (pinfunction "1_1") (pintype "passive"))
    )
    (net (code "73") (name "Net-(C38-Pad2)") (class "Default")
      (node (ref "C38") (pin "2") (pinfunction "2_2") (pintype "passive"))
      (node (ref "R43") (pin "1") (pinfunction "1_1") (pintype "passive"))
    )
    (net (code "74") (name "Net-(C42-Pad2)") (class "Default")
      (node (ref "C42") (pin "2") (pinfunction "2_2") (pintype "passive"))
      (node (ref "C47") (pin "2") (pinfunction "2_2") (pintype "passive"))
      (node (ref "R46") (pin "1") (pinfunction "1_1") (pintype "passive"))
      (node (ref "R53") (pin "2") (pinfunction "2_2") (pintype "passive"))
    )
    (net (code "75") (name "Net-(C43-Pad2)") (class "Default")
      (node (ref "C43") (pin "2") (pinfunction "2_2") (pintype "passive"))
      (node (ref "C48") (pin "2") (pinfunction "2_2") (pintype "passive"))
      (node (ref "R47") (pin "1") (pinfunction "1_1") (pintype "passive"))
      (node (ref "R54") (pin "2") (pinfunction "2_2") (pintype "passive"))
    )
    (net (code "76") (name "Net-(D1-Pad1)") (class "Default")
      (node (ref "D1") (pin "1") (pinfunction "1_1") (pintype "passive"))
      (node (ref "R1") (pin "1") (pinfunction "1_1") (pintype "passive"))
      (node (ref "R2") (pin "2") (pinfunction "2_2") (pintype "passive"))
    )
    (net (code "77") (name "Net-(D1-Pad2)") (class "Default")
      (node (ref "D1") (pin "2") (pinfunction "2_2") (pintype "passive"))
      (node (ref "Q1") (pin "5") (pinfunction "D_5") (pintype "passive"))
      (node (ref "Q1") (pin "6") (pinfunction "D_6") (pintype "passive"))
      (node (ref "Q1") (pin "7") (pinfunction "D_7") (pintype "passive"))
      (node (ref "Q1") (pin "8") (pinfunction "D_8") (pintype "passive"))
      (node (ref "R8") (pin "2") (pinfunction "2_2") (pintype "passive"))
    )
    (net (code "78") (name "Net-(D2-Pad1)") (class "Default")
      (node (ref "D2") (pin "1") (pinfunction "1_1") (pintype "passive"))
      (node (ref "R3") (pin "1") (pinfunction "1_1") (pintype "passive"))
      (node (ref "R4") (pin "2") (pinfunction "2_2") (pintype "passive"))
    )
    (net (code "79") (name "Net-(D2-Pad2)") (class "Default")
      (node (ref "D2") (pin "2") (pinfunction "2_2") (pintype "passive"))
      (node (ref "Q2") (pin "5") (pinfunction "D_5") (pintype "passive"))
      (node (ref "Q2") (pin "6") (pinfunction "D_6") (pintype "passive"))
      (node (ref "Q2") (pin "7") (pinfunction "D_7") (pintype "passive"))
      (node (ref "Q2") (pin "8") (pinfunction "D_8") (pintype "passive"))
      (node (ref "R10") (pin "2") (pinfunction "2_2") (pintype "passive"))
    )
    (net (code "80") (name "Net-(D3-Pad1)") (class "Default")
      (node (ref "D3") (pin "1") (pinfunction "1_1") (pintype "passive"))
      (node (ref "R5") (pin "1") (pinfunction "1_1") (pintype "passive"))
      (node (ref "R6") (pin "2") (pinfunction "2_2") (pintype "passive"))
    )
    (net (code "81") (name "Net-(D3-Pad2)") (class "Default")
      (node (ref "D3") (pin "2") (pinfunction "2_2") (pintype "passive"))
      (node (ref "Q3") (pin "5") (pinfunction "D_5") (pintype "passive"))
      (node (ref "Q3") (pin "6") (pinfunction "D_6") (pintype "passive"))
      (node (ref "Q3") (pin "7") (pinfunction "D_7") (pintype "passive"))
      (node (ref "Q3") (pin "8") (pinfunction "D_8") (pintype "passive"))
      (node (ref "R12") (pin "2") (pinfunction "2_2") (pintype "passive"))
    )
    (net (code "82") (name "Net-(Q1-G)") (class "Default")
      (node (ref "Q1") (pin "4") (pinfunction "G_4") (pintype "passive"))
      (node (ref "R13") (pin "1") (pinfunction "1_1") (pintype "passive"))
    )
    (net (code "83") (name "Net-(Q1-S-Pad1)") (class "Default")
      (node (ref "Q1") (pin "1") (pinfunction "S_1") (pintype "passive"))
      (node (ref "Q1") (pin "2") (pinfunction "S_2") (pintype "passive"))
      (node (ref "Q1") (pin "3") (pinfunction "S_3") (pintype "passive"))
      (node (ref "R19") (pin "1") (pinfunction "1_1") (pintype "passive"))
      (node (ref "R22") (pin "1") (pinfunction "1_1") (pintype "passive"))
    )
    (net (code "84") (name "Net-(Q2-G)") (class "Default")
      (node (ref "Q2") (pin "4") (pinfunction "G_4") (pintype "passive"))
      (node (ref "R14") (pin "1") (pinfunction "1_1") (pintype "passive"))
    )
    (net (code "85") (name "Net-(Q2-S-Pad1)") (class "Default")
      (node (ref "Q2") (pin "1") (pinfunction "S_1") (pintype "passive"))
      (node (ref "Q2") (pin "2") (pinfunction "S_2") (pintype "passive"))
      (node (ref "Q2") (pin "3") (pinfunction "S_3") (pintype "passive"))
      (node (ref "R20") (pin "1") (pinfunction "1_1") (pintype "passive"))
      (node (ref "R23") (pin "1") (pinfunction "1_1") (pintype "passive"))
    )
    (net (code "86") (name "Net-(Q3-G)") (class "Default")
      (node (ref "Q3") (pin "4") (pinfunction "G_4") (pintype "passive"))
      (node (ref "R15") (pin "1") (pinfunction "1_1") (pintype "passive"))
    )
    (net (code "87") (name "Net-(Q3-S-Pad1)") (class "Default")
      (node (ref "Q3") (pin "1") (pinfunction "S_1") (pintype "passive"))
      (node (ref "Q3") (pin "2") (pinfunction "S_2") (pintype "passive"))
      (node (ref "Q3") (pin "3") (pinfunction "S_3") (pintype "passive"))
      (node (ref "R21") (pin "1") (pinfunction "1_1") (pintype "passive"))
      (node (ref "R24") (pin "1") (pinfunction "1_1") (pintype "passive"))
    )
    (net (code "88") (name "Net-(Q4-B)") (class "Default")
      (node (ref "Q4") (pin "2") (pinfunction "B_2") (pintype "passive"))
      (node (ref "R48") (pin "1") (pinfunction "1_1") (pintype "passive"))
    )
    (net (code "89") (name "Net-(Q4-C)") (class "Default")
      (node (ref "Q4") (pin "1") (pinfunction "C_1") (pintype "passive"))
      (node (ref "R40") (pin "2") (pinfunction "2_2") (pintype "passive"))
    )
    (net (code "90") (name "Net-(Q4-E)") (class "Default")
      (node (ref "Q4") (pin "3") (pinfunction "E_3") (pintype "passive"))
      (node (ref "R55") (pin "1") (pinfunction "1_1") (pintype "passive"))
      (node (ref "U5") (pin "6") (pinfunction "-IN2_6") (pintype "passive"))
    )
    (net (code "91") (name "Net-(Q5-B)") (class "Default")
      (node (ref "Q5") (pin "2") (pinfunction "B_2") (pintype "passive"))
      (node (ref "R62") (pin "1") (pinfunction "1_1") (pintype "passive"))
    )
    (net (code "92") (name "Net-(Q5-C)") (class "Default")
      (node (ref "Q5") (pin "1") (pinfunction "C_1") (pintype "passive"))
      (node (ref "R58") (pin "2") (pinfunction "2_2") (pintype "passive"))
    )
    (net (code "93") (name "Net-(Q5-E)") (class "Default")
      (node (ref "Q5") (pin "3") (pinfunction "E_3") (pintype "passive"))
      (node (ref "R65") (pin "1") (pinfunction "1_1") (pintype "passive"))
      (node (ref "U12") (pin "6") (pinfunction "-IN2_6") (pintype "passive"))
    )
    (net (code "94") (name "Net-(R34-Pad2)") (class "Default")
      (node (ref "R34") (pin "2") (pinfunction "2_2") (pintype "passive"))
      (node (ref "R37") (pin "2") (pinfunction "2_2") (pintype "passive"))
      (node (ref "U4") (pin "1") (pinfunction "VIN-_1") (pintype "passive"))
      (node (ref "U4") (pin "2") (pinfunction "VIN-_2") (pintype "passive"))
    )
    (net (code "95") (name "Net-(R44-Pad1)") (class "Default")
      (node (ref "R44") (pin "1") (pinfunction "1_1") (pintype "passive"))
      (node (ref "R45") (pin "2") (pinfunction "2_2") (pintype "passive"))
      (node (ref "R52") (pin "1") (pinfunction "1_1") (pintype "passive"))
    )
    (net (code "96") (name "Net-(R56-Pad2)") (class "Default")
      (node (ref "R56") (pin "2") (pinfunction "2_2") (pintype "passive"))
      (node (ref "R57") (pin "2") (pinfunction "2_2") (pintype "passive"))
      (node (ref "U11") (pin "1") (pinfunction "VIN-_1") (pintype "passive"))
      (node (ref "U11") (pin "2") (pinfunction "VIN-_2") (pintype "passive"))
    )
    (net (code "97") (name "Net-(R60-Pad1)") (class "Default")
      (node (ref "R60") (pin "1") (pinfunction "1_1") (pintype "passive"))
      (node (ref "R61") (pin "2") (pinfunction "2_2") (pintype "passive"))
      (node (ref "R64") (pin "1") (pinfunction "1_1") (pintype "passive"))
    )
    (net (code "98") (name "Net-(U1-HOLD)") (class "Default")
      (node (ref "R26") (pin "2") (pinfunction "2_2") (pintype "passive"))
      (node (ref "U1") (pin "4") (pinfunction "HOLD_4") (pintype "passive"))
    )
    (net (code "99") (name "Net-(U1-KEEP)") (class "Default")
      (node (ref "C19") (pin "2") (pinfunction "2_2") (pintype "passive"))
      (node (ref "U1") (pin "2") (pinfunction "KEEP_2") (pintype "passive"))
    )
    (net (code "100") (name "Net-(U1-OSC)") (class "Default")
      (node (ref "R27") (pin "2") (pinfunction "2_2") (pintype "passive"))
      (node (ref "U1") (pin "5") (pinfunction "OSC_5") (pintype "passive"))
    )
    (net (code "101") (name "Net-(U1-OUT)") (class "Default")
      (node (ref "R13") (pin "2") (pinfunction "2_2") (pintype "passive"))
      (node (ref "U1") (pin "11") (pinfunction "OUT_11") (pintype "passive"))
    )
    (net (code "102") (name "Net-(U1-PEAK)") (class "Default")
      (node (ref "R25") (pin "2") (pinfunction "2_2") (pintype "passive"))
      (node (ref "U1") (pin "3") (pinfunction "PEAK_3") (pintype "passive"))
    )
    (net (code "103") (name "Net-(U1-SENSE)") (class "Default")
      (node (ref "C16") (pin "2") (pinfunction "2_2") (pintype "passive"))
      (node (ref "R19") (pin "2") (pinfunction "2_2") (pintype "passive"))
      (node (ref "U1") (pin "9") (pinfunction "SENSE_9") (pintype "passive"))
    )
    (net (code "104") (name "Net-(U1-VIN)") (class "Default")
      (node (ref "C8") (pin "2") (pinfunction "2_2") (pintype "passive"))
      (node (ref "R7") (pin "1") (pinfunction "1_1") (pintype "passive"))
      (node (ref "U1") (pin "7") (pinfunction "VIN_7") (pintype "passive"))
    )
    (net (code "105") (name "Net-(U2-HOLD)") (class "Default")
      (node (ref "R29") (pin "2") (pinfunction "2_2") (pintype "passive"))
      (node (ref "U2") (pin "4") (pinfunction "HOLD_4") (pintype "passive"))
    )
    (net (code "106") (name "Net-(U2-KEEP)") (class "Default")
      (node (ref "C20") (pin "2") (pinfunction "2_2") (pintype "passive"))
      (node (ref "U2") (pin "2") (pinfunction "KEEP_2") (pintype "passive"))
    )
    (net (code "107") (name "Net-(U2-OSC)") (class "Default")
      (node (ref "R30") (pin "2") (pinfunction "2_2") (pintype "passive"))
      (node (ref "U2") (pin "5") (pinfunction "OSC_5") (pintype "passive"))
    )
    (net (code "108") (name "Net-(U2-OUT)") (class "Default")
      (node (ref "R14") (pin "2") (pinfunction "2_2") (pintype "passive"))
      (node (ref "U2") (pin "11") (pinfunction "OUT_11") (pintype "passive"))
    )
    (net (code "109") (name "Net-(U2-PEAK)") (class "Default")
      (node (ref "R28") (pin "2") (pinfunction "2_2") (pintype "passive"))
      (node (ref "U2") (pin "3") (pinfunction "PEAK_3") (pintype "passive"))
    )
    (net (code "110") (name "Net-(U2-SENSE)") (class "Default")
      (node (ref "C17") (pin "2") (pinfunction "2_2") (pintype "passive"))
      (node (ref "R20") (pin "2") (pinfunction "2_2") (pintype "passive"))
      (node (ref "U2") (pin "9") (pinfunction "SENSE_9") (pintype "passive"))
    )
    (net (code "111") (name "Net-(U2-VIN)") (class "Default")
      (node (ref "C10") (pin "2") (pinfunction "2_2") (pintype "passive"))
      (node (ref "R9") (pin "1") (pinfunction "1_1") (pintype "passive"))
      (node (ref "U2") (pin "7") (pinfunction "VIN_7") (pintype "passive"))
    )
    (net (code "112") (name "Net-(U3-HOLD)") (class "Default")
      (node (ref "R32") (pin "2") (pinfunction "2_2") (pintype "passive"))
      (node (ref "U3") (pin "4") (pinfunction "HOLD_4") (pintype "passive"))
    )
    (net (code "113") (name "Net-(U3-KEEP)") (class "Default")
      (node (ref "C21") (pin "2") (pinfunction "2_2") (pintype "passive"))
      (node (ref "U3") (pin "2") (pinfunction "KEEP_2") (pintype "passive"))
    )
    (net (code "114") (name "Net-(U3-OSC)") (class "Default")
      (node (ref "R33") (pin "2") (pinfunction "2_2") (pintype "passive"))
      (node (ref "U3") (pin "5") (pinfunction "OSC_5") (pintype "passive"))
    )
    (net (code "115") (name "Net-(U3-OUT)") (class "Default")
      (node (ref "R15") (pin "2") (pinfunction "2_2") (pintype "passive"))
      (node (ref "U3") (pin "11") (pinfunction "OUT_11") (pintype "passive"))
    )
    (net (code "116") (name "Net-(U3-PEAK)") (class "Default")
      (node (ref "R31") (pin "2") (pinfunction "2_2") (pintype "passive"))
      (node (ref "U3") (pin "3") (pinfunction "PEAK_3") (pintype "passive"))
    )
    (net (code "117") (name "Net-(U3-SENSE)") (class "Default")
      (node (ref "C18") (pin "2") (pinfunction "2_2") (pintype "passive"))
      (node (ref "R21") (pin "2") (pinfunction "2_2") (pintype "passive"))
      (node (ref "U3") (pin "9") (pinfunction "SENSE_9") (pintype "passive"))
    )
    (net (code "118") (name "Net-(U3-VIN)") (class "Default")
      (node (ref "C12") (pin "2") (pinfunction "2_2") (pintype "passive"))
      (node (ref "R11") (pin "1") (pinfunction "1_1") (pintype "passive"))
      (node (ref "U3") (pin "7") (pinfunction "VIN_7") (pintype "passive"))
    )
    (net (code "119") (name "Net-(U4-VS)") (class "Default")
      (node (ref "C22") (pin "2") (pinfunction "2_2") (pintype "passive"))
      (node (ref "FB1") (pin "2") (pinfunction "2_2") (pintype "passive"))
      (node (ref "U4") (pin "4") (pinfunction "VS_4") (pintype "passive"))
    )
    (net (code "120") (name "Net-(U5A-+IN1)") (class "Default")
      (node (ref "C44") (pin "2") (pinfunction "2_2") (pintype "passive"))
      (node (ref "R41") (pin "1") (pinfunction "1_1") (pintype "passive"))
      (node (ref "R49") (pin "1") (pinfunction "1_1") (pintype "passive"))
      (node (ref "U5") (pin "3") (pinfunction "+IN1_3") (pintype "passive"))
    )
    (net (code "121") (name "Net-(U5A--IN1)") (class "Default")
      (node (ref "R44") (pin "2") (pinfunction "2_2") (pintype "passive"))
      (node (ref "U5") (pin "1") (pinfunction "OUT1_1") (pintype "passive"))
      (node (ref "U5") (pin "2") (pinfunction "-IN1_2") (pintype "passive"))
    )
    (net (code "122") (name "Net-(U5B-+IN2)") (class "Default")
      (node (ref "R45") (pin "1") (pinfunction "1_1") (pintype "passive"))
      (node (ref "U5") (pin "5") (pinfunction "+IN2_5") (pintype "passive"))
    )
    (net (code "123") (name "Net-(U5B-OUT2)") (class "Default")
      (node (ref "R48") (pin "2") (pinfunction "2_2") (pintype "passive"))
      (node (ref "U5") (pin "7") (pinfunction "OUT2_7") (pintype "passive"))
    )
    (net (code "124") (name "Net-(U6-BSTN)") (class "Default")
      (node (ref "C40") (pin "2") (pinfunction "2_2") (pintype "passive"))
      (node (ref "U6") (pin "10") (pinfunction "BSTN_10") (pintype "passive"))
    )
    (net (code "125") (name "Net-(U6-BSTP)") (class "Default")
      (node (ref "C23") (pin "2") (pinfunction "2_2") (pintype "passive"))
      (node (ref "U6") (pin "13") (pinfunction "BSTP_13") (pintype "passive"))
    )
    (net (code "126") (name "Net-(U6-IN+)") (class "Default")
      (node (ref "C42") (pin "1") (pinfunction "1_1") (pintype "passive"))
      (node (ref "U6") (pin "6") (pinfunction "IN+_6") (pintype "passive"))
    )
    (net (code "127") (name "Net-(U6-IN-)") (class "Default")
      (node (ref "C51") (pin "2") (pinfunction "2_2") (pintype "passive"))
      (node (ref "U6") (pin "7") (pinfunction "IN-_7") (pintype "passive"))
    )
    (net (code "128") (name "Net-(U6-OUT+)") (class "Default")
      (node (ref "C23") (pin "1") (pinfunction "1_1") (pintype "passive"))
      (node (ref "R35") (pin "2") (pinfunction "2_2") (pintype "passive"))
      (node (ref "R38") (pin "2") (pinfunction "2_2") (pintype "passive"))
      (node (ref "U6") (pin "12") (pinfunction "OUT+_12") (pintype "passive"))
    )
    (net (code "129") (name "Net-(U6-OUT-)") (class "Default")
      (node (ref "C40") (pin "1") (pinfunction "1_1") (pintype "passive"))
      (node (ref "R42") (pin "2") (pinfunction "2_2") (pintype "passive"))
      (node (ref "R50") (pin "2") (pinfunction "2_2") (pintype "passive"))
      (node (ref "U6") (pin "11") (pinfunction "OUT-_11") (pintype "passive"))
    )
    (net (code "130") (name "Net-(U6-REG)") (class "Default")
      (node (ref "C49") (pin "2") (pintype "passive"))
      (node (ref "U6") (pin "3") (pinfunction "REG_3") (pintype "passive"))
    )
    (net (code "131") (name "Net-(U7-BSTN)") (class "Default")
      (node (ref "C41") (pin "2") (pinfunction "2_2") (pintype "passive"))
      (node (ref "U7") (pin "10") (pinfunction "BSTN_10") (pintype "passive"))
    )
    (net (code "132") (name "Net-(U7-BSTP)") (class "Default")
      (node (ref "C24") (pin "2") (pinfunction "2_2") (pintype "passive"))
      (node (ref "U7") (pin "13") (pinfunction "BSTP_13") (pintype "passive"))
    )
    (net (code "133") (name "Net-(U7-IN+)") (class "Default")
      (node (ref "C43") (pin "1") (pinfunction "1_1") (pintype "passive"))
      (node (ref "U7") (pin "6") (pinfunction "IN+_6") (pintype "passive"))
    )
    (net (code "134") (name "Net-(U7-IN-)") (class "Default")
      (node (ref "C52") (pin "2") (pinfunction "2_2") (pintype "passive"))
      (node (ref "U7") (pin "7") (pinfunction "IN-_7") (pintype "passive"))
    )
    (net (code "135") (name "Net-(U7-OUT+)") (class "Default")
      (node (ref "C24") (pin "1") (pinfunction "1_1") (pintype "passive"))
      (node (ref "R36") (pin "2") (pinfunction "2_2") (pintype "passive"))
      (node (ref "R39") (pin "2") (pinfunction "2_2") (pintype "passive"))
      (node (ref "U7") (pin "12") (pinfunction "OUT+_12") (pintype "passive"))
    )
    (net (code "136") (name "Net-(U7-OUT-)") (class "Default")
      (node (ref "C41") (pin "1") (pinfunction "1_1") (pintype "passive"))
      (node (ref "R43") (pin "2") (pinfunction "2_2") (pintype "passive"))
      (node (ref "R51") (pin "2") (pinfunction "2_2") (pintype "passive"))
      (node (ref "U7") (pin "11") (pinfunction "OUT-_11") (pintype "passive"))
    )
    (net (code "137") (name "Net-(U7-REG)") (class "Default")
      (node (ref "C50") (pin "2") (pintype "passive"))
      (node (ref "U7") (pin "3") (pinfunction "REG_3") (pintype "passive"))
    )
    (net (code "138") (name "Net-(U11-VS)") (class "Default")
      (node (ref "C53") (pin "2") (pinfunction "2_2") (pintype "passive"))
      (node (ref "FB2") (pin "2") (pinfunction "2_2") (pintype "passive"))
      (node (ref "U11") (pin "4") (pinfunction "VS_4") (pintype "passive"))
    )
    (net (code "139") (name "Net-(U12A-+IN1)") (class "Default")
      (node (ref "C57") (pin "2") (pinfunction "2_2") (pintype "passive"))
      (node (ref "R59") (pin "1") (pinfunction "1_1") (pintype "passive"))
      (node (ref "R63") (pin "1") (pinfunction "1_1") (pintype "passive"))
      (node (ref "U12") (pin "3") (pinfunction "+IN1_3") (pintype "passive"))
    )
    (net (code "140") (name "Net-(U12A--IN1)") (class "Default")
      (node (ref "R60") (pin "2") (pinfunction "2_2") (pintype "passive"))
      (node (ref "U12") (pin "1") (pinfunction "OUT1_1") (pintype "passive"))
      (node (ref "U12") (pin "2") (pinfunction "-IN1_2") (pintype "passive"))
    )
    (net (code "141") (name "Net-(U12B-+IN2)") (class "Default")
      (node (ref "R61") (pin "1") (pinfunction "1_1") (pintype "passive"))
      (node (ref "U12") (pin "5") (pinfunction "+IN2_5") (pintype "passive"))
    )
    (net (code "142") (name "Net-(U12B-OUT2)") (class "Default")
      (node (ref "R62") (pin "2") (pinfunction "2_2") (pintype "passive"))
      (node (ref "U12") (pin "7") (pinfunction "OUT2_7") (pintype "passive"))
    )
    (net (code "143") (name "VDD_3V3") (class "Default")
      (node (ref "FB1") (pin "1") (pinfunction "1_1") (pintype "passive"))
      (node (ref "FB2") (pin "1") (pinfunction "1_1") (pintype "passive"))
      (node (ref "P1") (pin "18") (pinfunction "18_18") (pintype "passive"))
      (node (ref "R16") (pin "2") (pinfunction "2_2") (pintype "passive"))
      (node (ref "R17") (pin "2") (pinfunction "2_2") (pintype "passive"))
      (node (ref "R18") (pin "2") (pinfunction "2_2") (pintype "passive"))
    )
    (net (code "144") (name "VDD_5V0") (class "Default")
      (node (ref "C25") (pin "2") (pinfunction "2_2") (pintype "passive"))
      (node (ref "C54") (pin "2") (pinfunction "2_2") (pintype "passive"))
      (node (ref "P1") (pin "22") (pinfunction "22_22") (pintype "passive"))
      (node (ref "U12") (pin "8") (pinfunction "+VS_8") (pintype "passive"))
      (node (ref "U5") (pin "8") (pinfunction "+VS_8") (pintype "passive"))
    )
    (net (code "145") (name "unconnected-(U1-NC-Pad1)") (class "Default")
      (node (ref "U1") (pin "1") (pinfunction "NC_1") (pintype "passive+no_connect"))
    )
    (net (code "146") (name "unconnected-(U1-NC-Pad6)") (class "Default")
      (node (ref "U1") (pin "6") (pinfunction "NC_6") (pintype "passive+no_connect"))
    )
    (net (code "147") (name "unconnected-(U1-NC-Pad10)") (class "Default")
      (node (ref "U1") (pin "10") (pinfunction "NC_10") (pintype "passive+no_connect"))
    )
    (net (code "148") (name "unconnected-(U1-NC-Pad14)") (class "Default")
      (node (ref "U1") (pin "14") (pinfunction "NC_14") (pintype "passive+no_connect"))
    )
    (net (code "149") (name "unconnected-(U2-NC-Pad1)") (class "Default")
      (node (ref "U2") (pin "1") (pinfunction "NC_1") (pintype "passive+no_connect"))
    )
    (net (code "150") (name "unconnected-(U2-NC-Pad6)") (class "Default")
      (node (ref "U2") (pin "6") (pinfunction "NC_6") (pintype "passive+no_connect"))
    )
    (net (code "151") (name "unconnected-(U2-NC-Pad10)") (class "Default")
      (node (ref "U2") (pin "10") (pinfunction "NC_10") (pintype "passive+no_connect"))
    )
    (net (code "152") (name "unconnected-(U2-NC-Pad14)") (class "Default")
      (node (ref "U2") (pin "14") (pinfunction "NC_14") (pintype "passive+no_connect"))
    )
    (net (code "153") (name "unconnected-(U3-NC-Pad1)") (class "Default")
      (node (ref "U3") (pin "1") (pinfunction "NC_1") (pintype "passive+no_connect"))
    )
    (net (code "154") (name "unconnected-(U3-NC-Pad6)") (class "Default")
      (node (ref "U3") (pin "6") (pinfunction "NC_6") (pintype "passive+no_connect"))
    )
    (net (code "155") (name "unconnected-(U3-NC-Pad10)") (class "Default")
      (node (ref "U3") (pin "10") (pinfunction "NC_10") (pintype "passive+no_connect"))
    )
    (net (code "156") (name "unconnected-(U3-NC-Pad14)") (class "Default")
      (node (ref "U3") (pin "14") (pinfunction "NC_14") (pintype "passive+no_connect"))
    )
    (net (code "157") (name "unconnected-(U10-Pad7)") (class "Default")
      (node (ref "U10") (pin "7") (pinfunction "7_7") (pintype "passive+no_connect"))
    )
    (net (code "158") (name "unconnected-(U10-Pad8)") (class "Default")
      (node (ref "U10") (pin "8") (pinfunction "8_8") (pintype "passive+no_connect"))
    )
  )
)
